# EEZ_DIB_MCU_r1B5.net
KiCad netlist of a schematic drawn in EAGLE
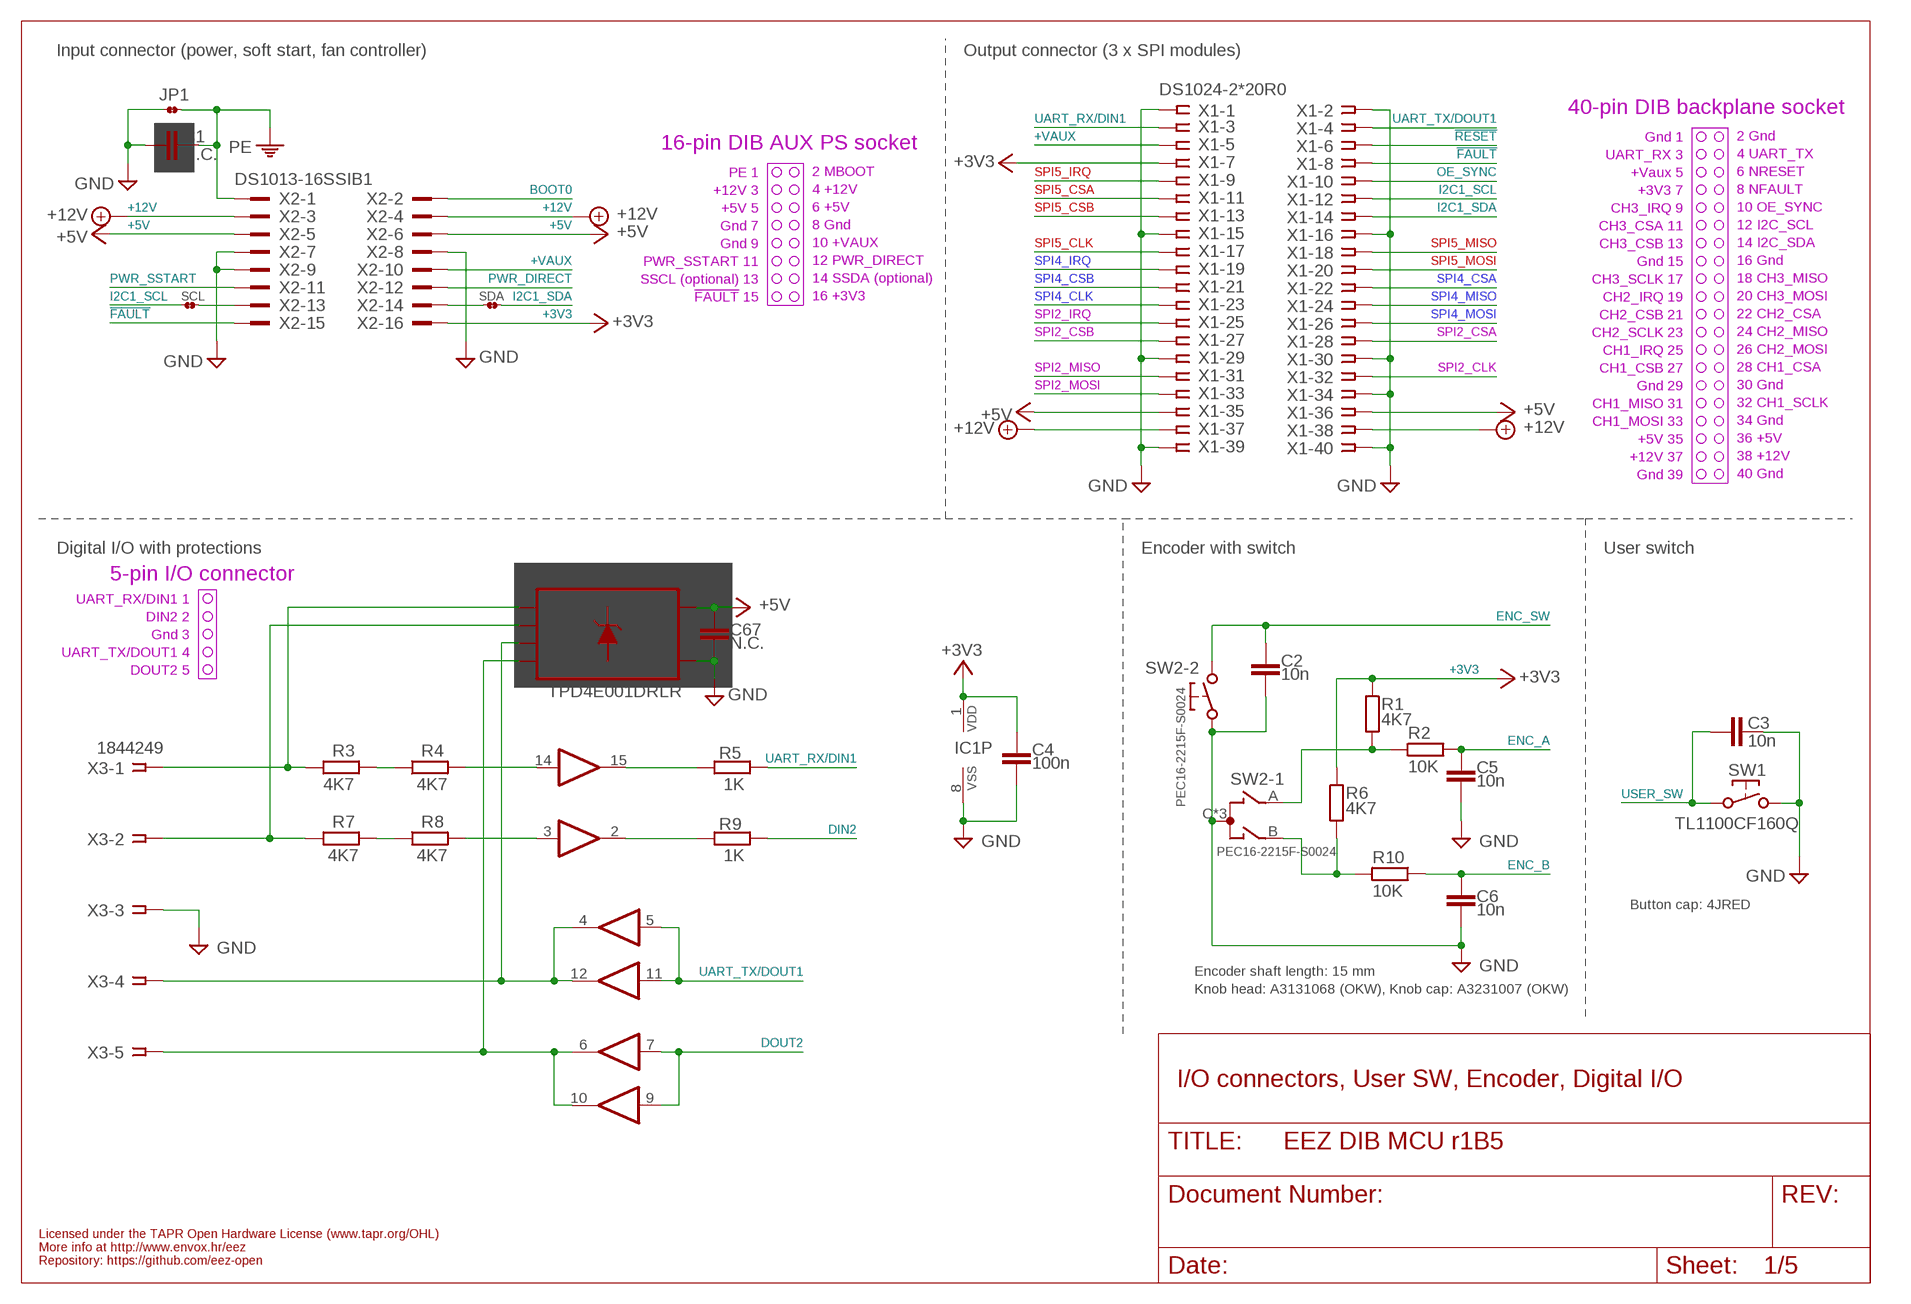
[diagram p0: schematic, sheet 1]
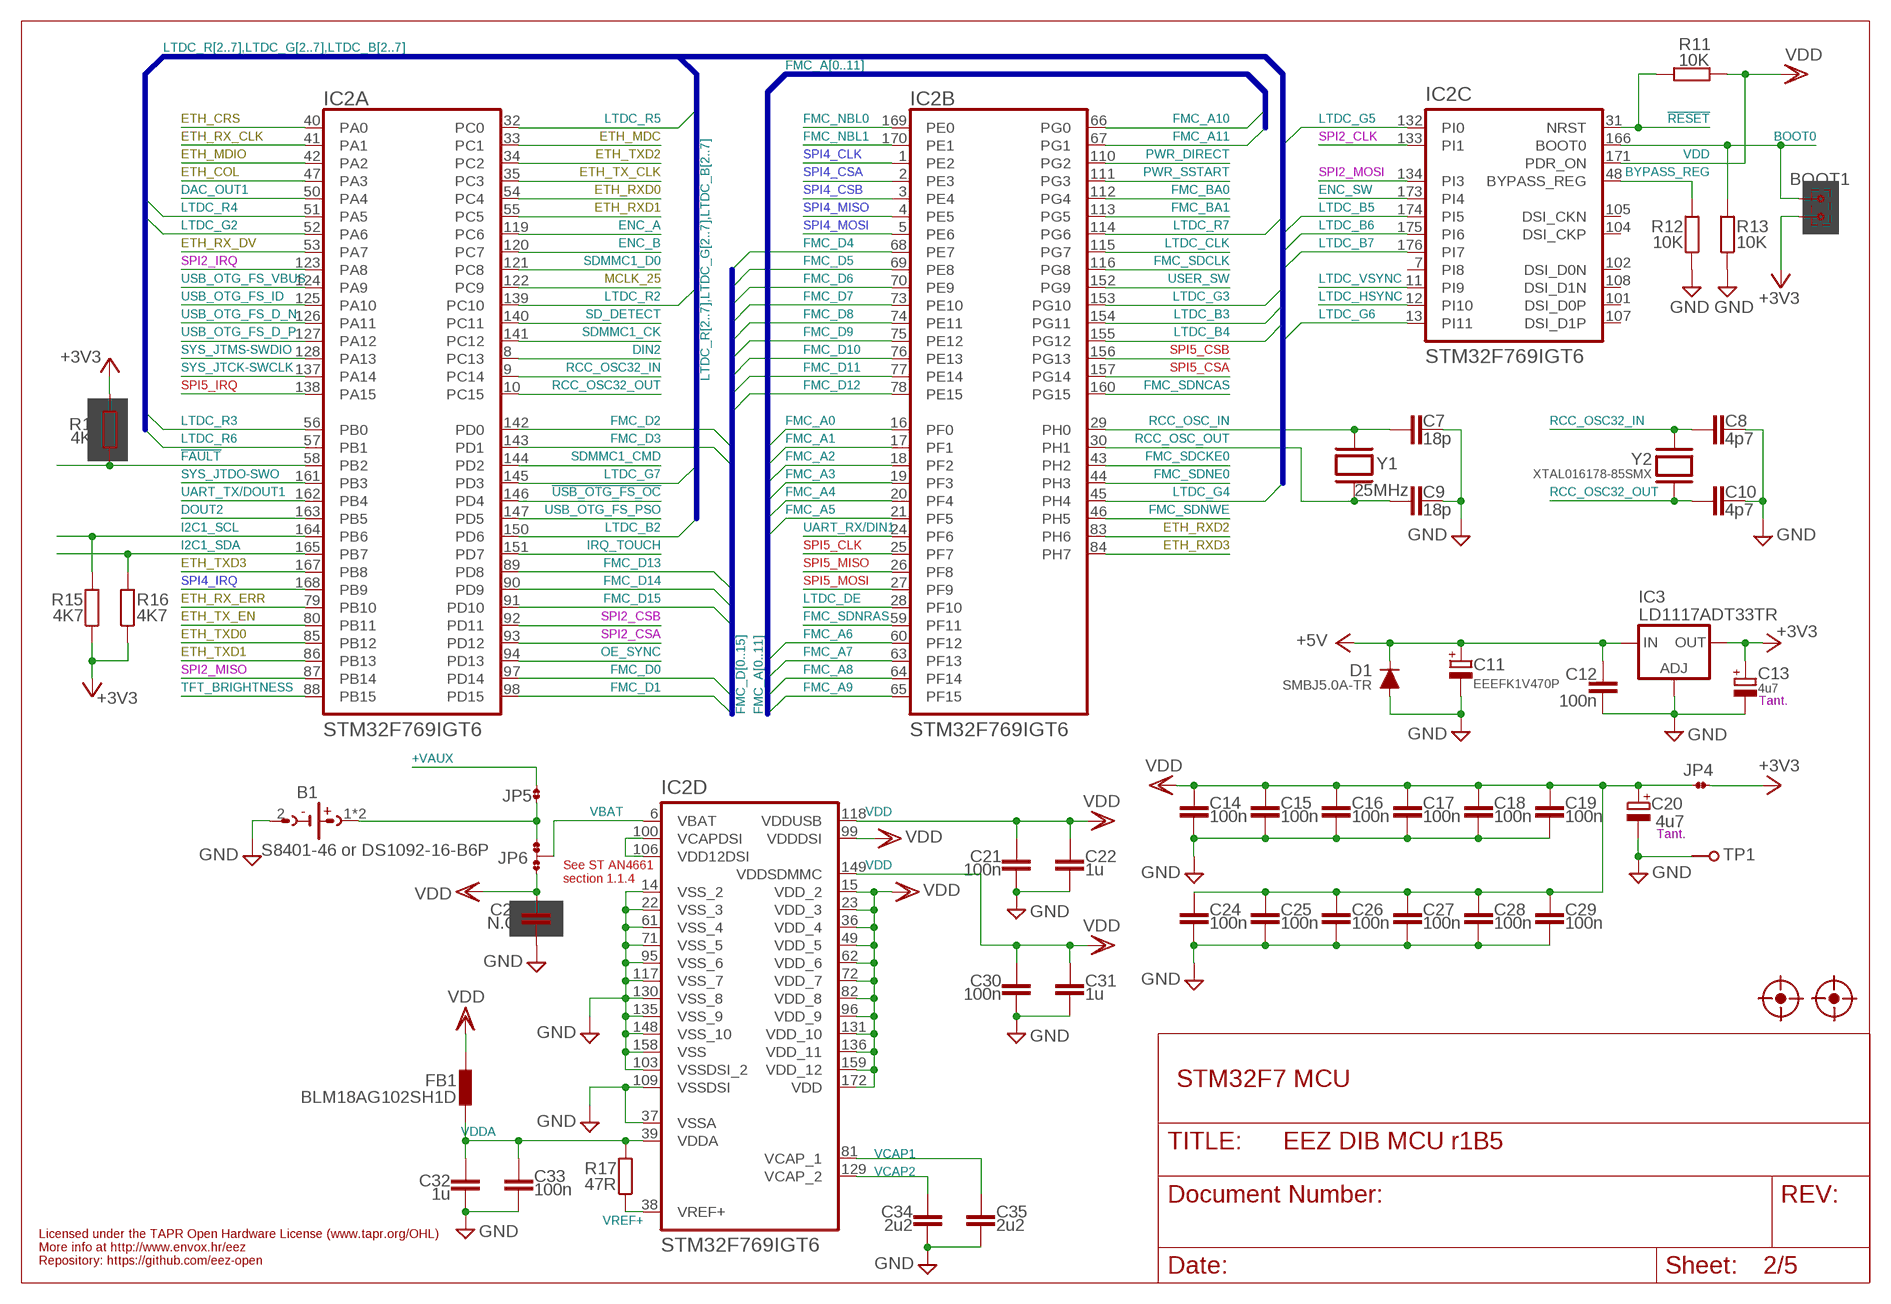
[diagram p1: schematic, sheet 2]
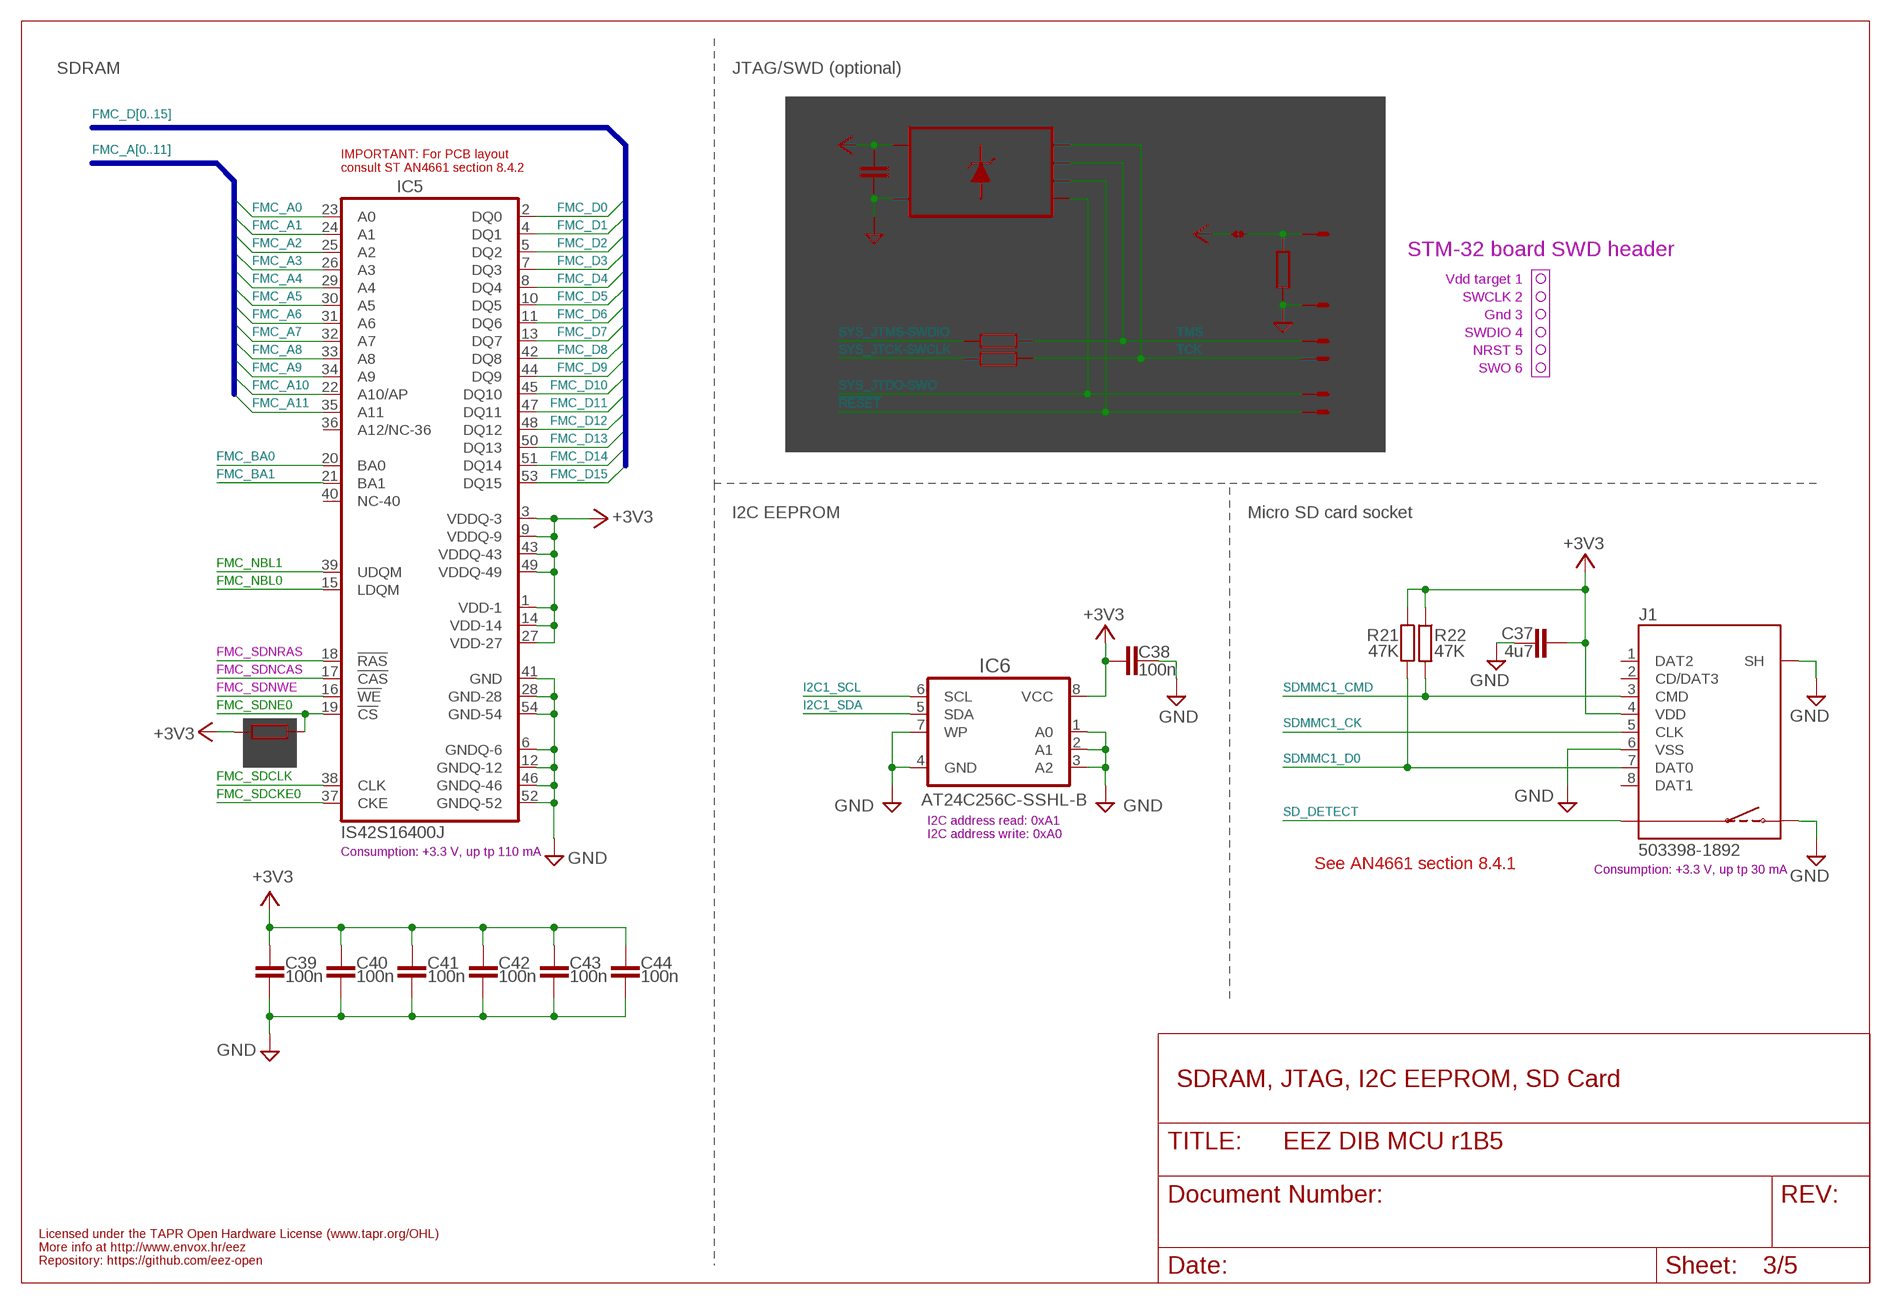
[diagram p2: schematic, sheet 3]
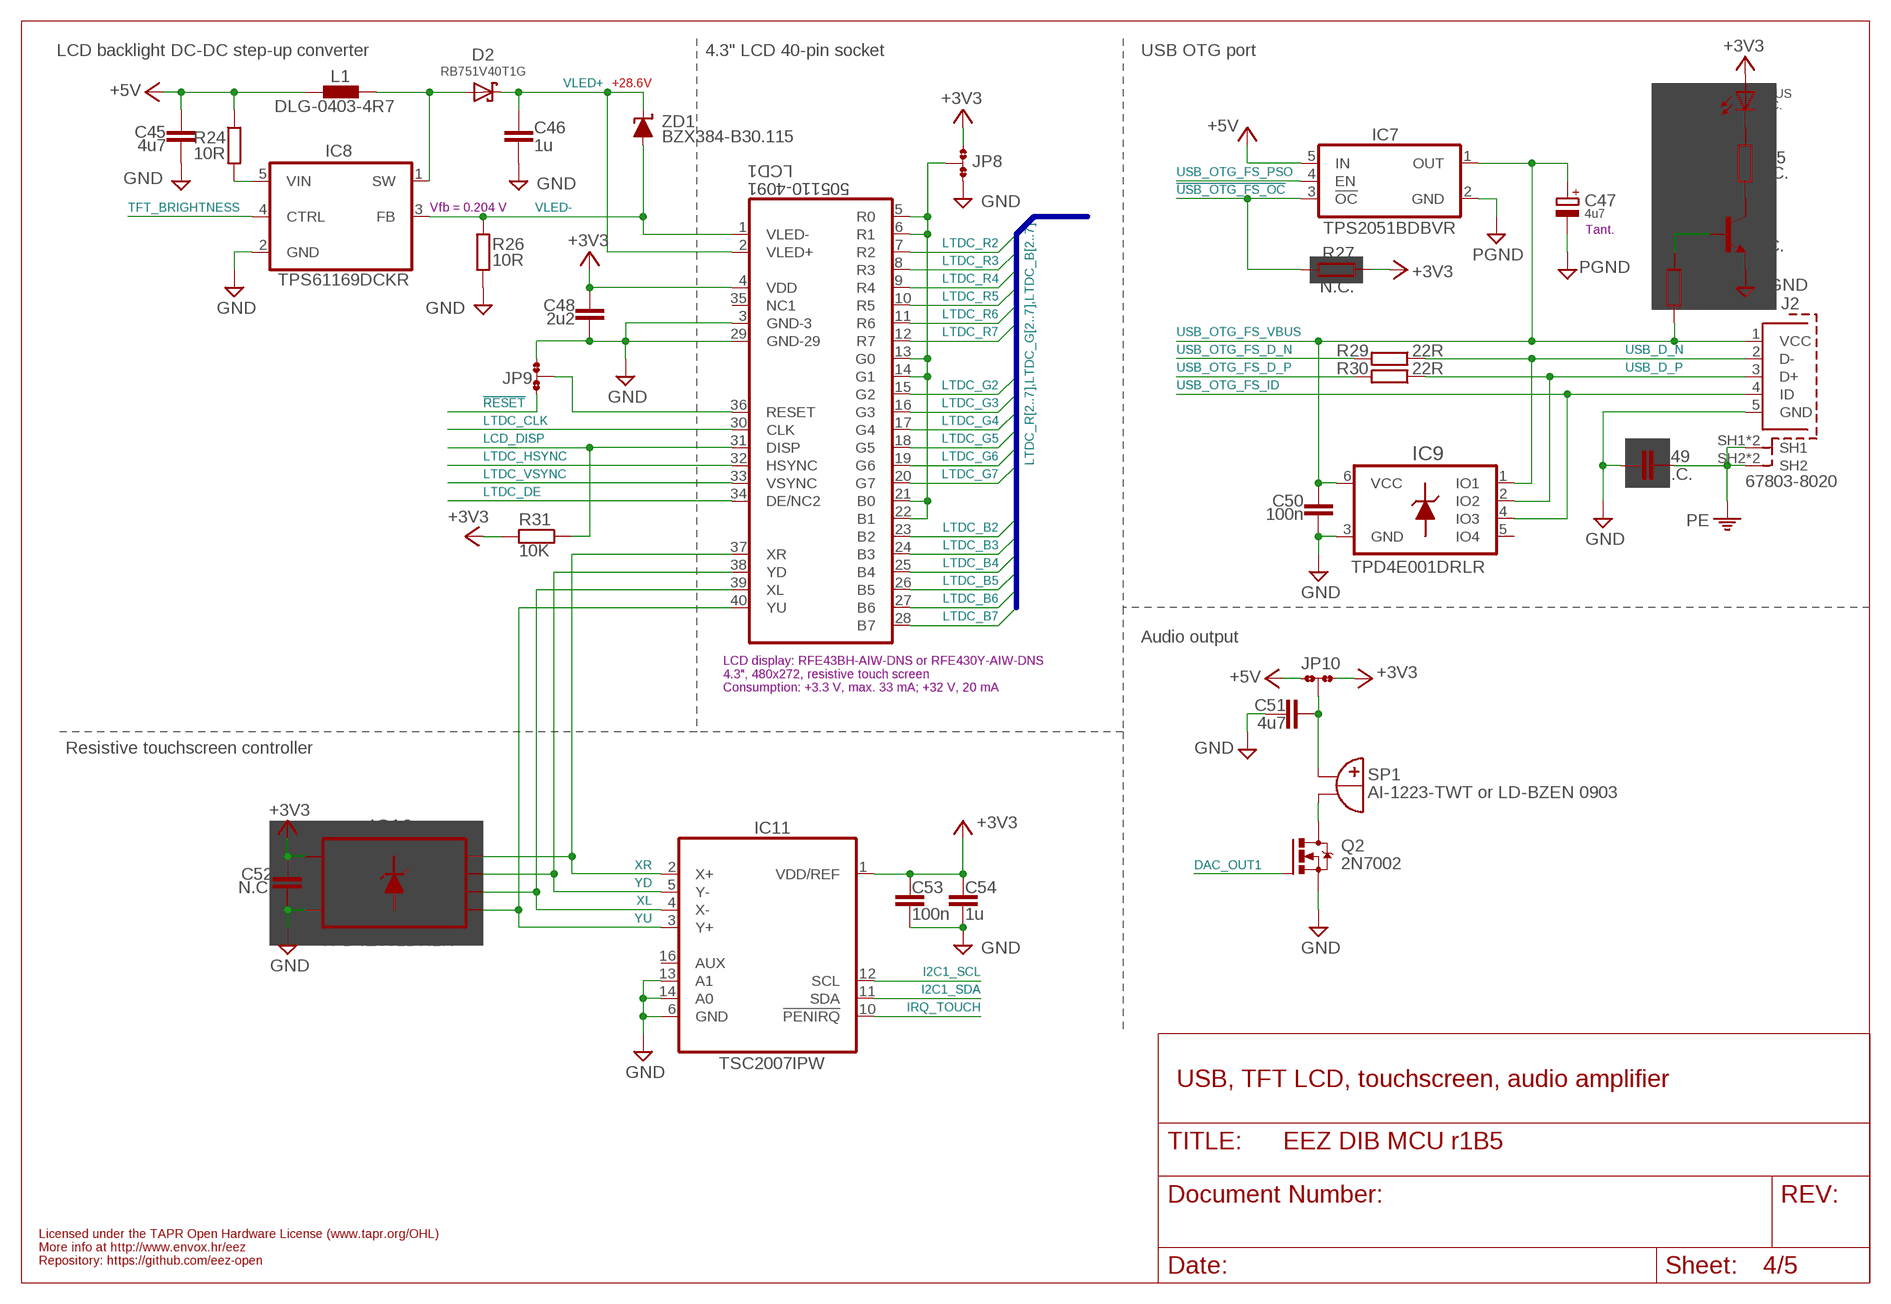
[diagram p3: schematic, sheet 4]
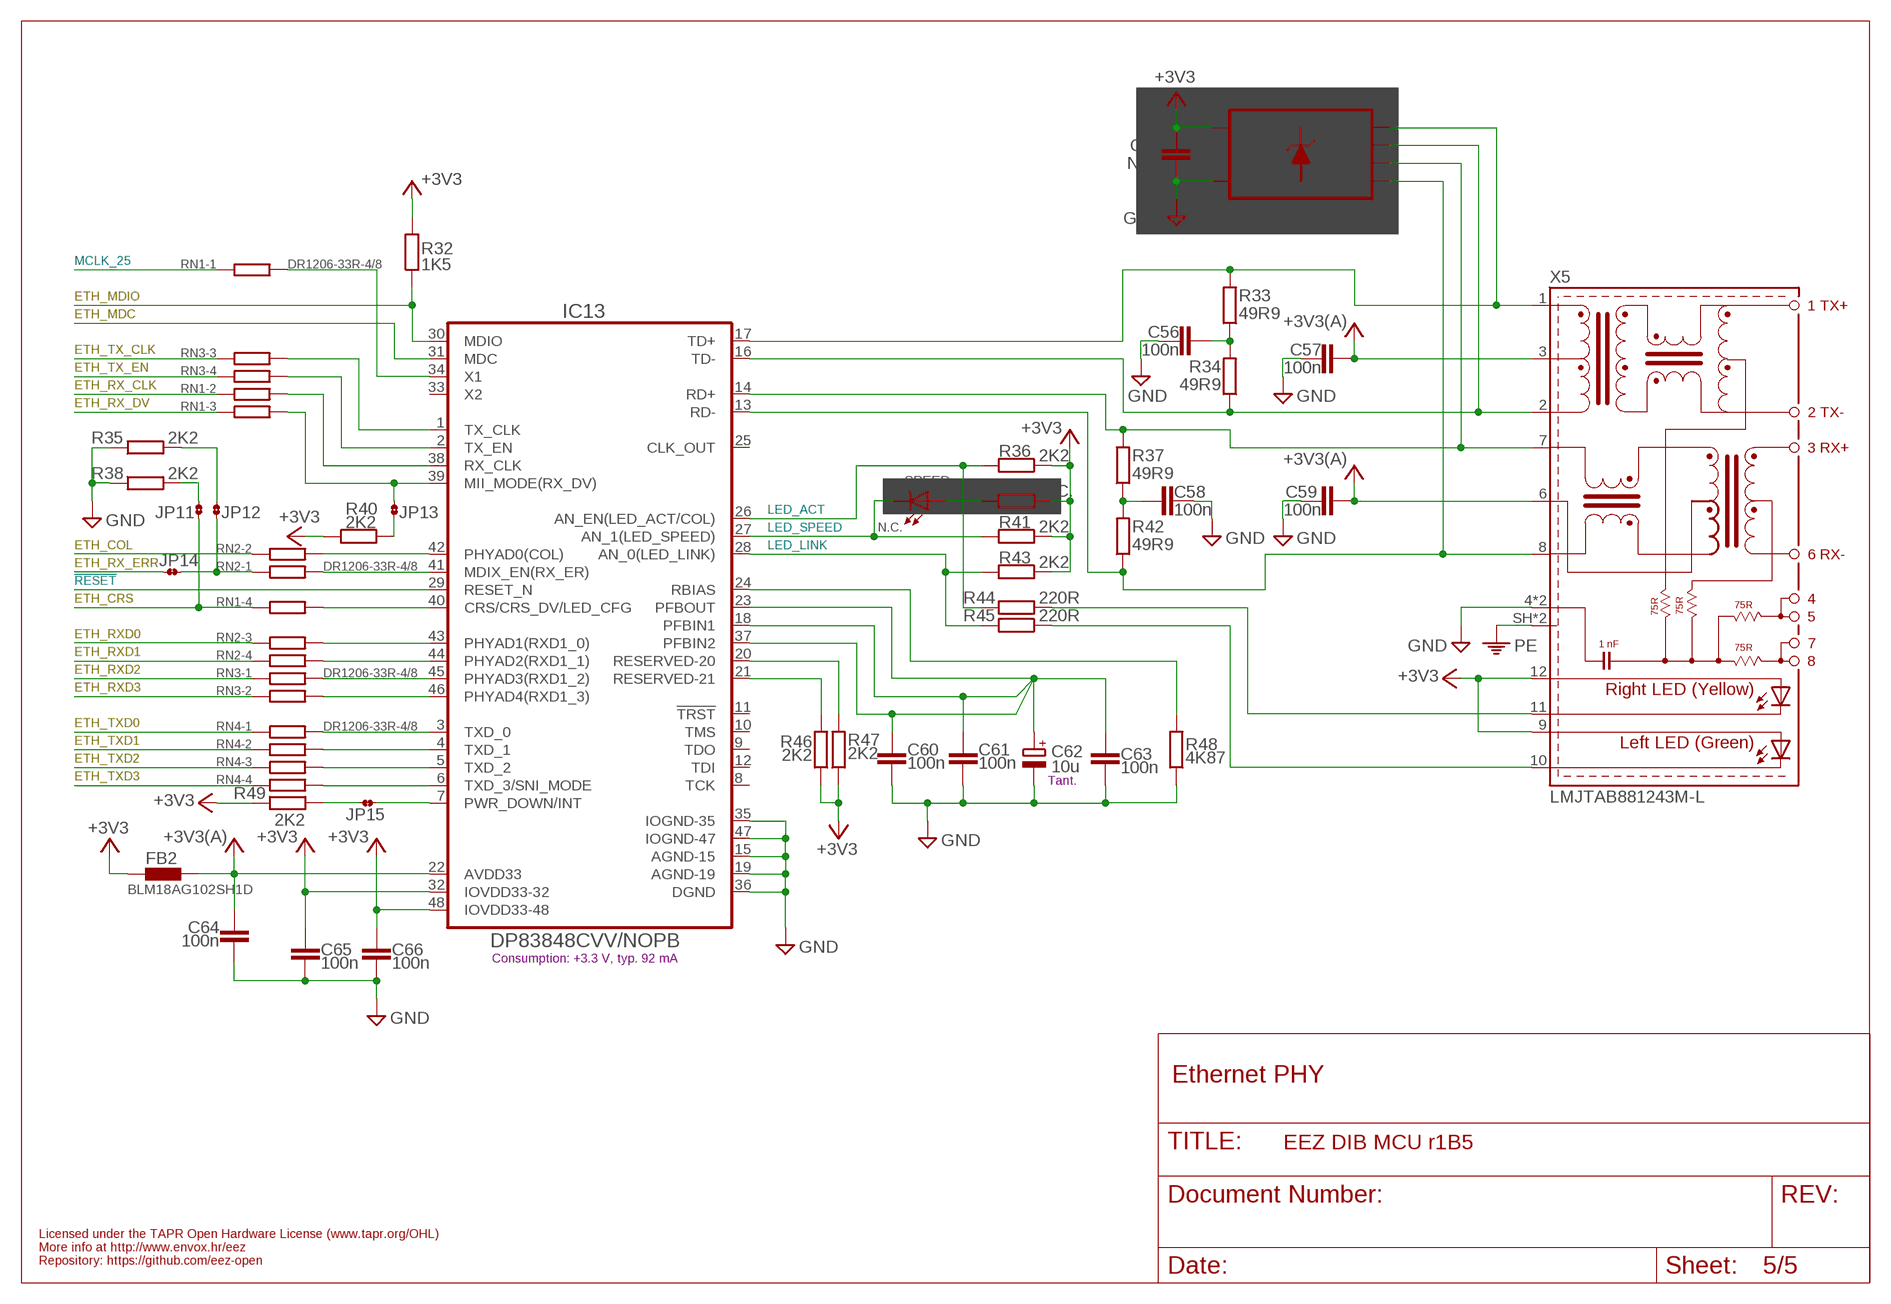
[diagram p4: schematic, sheet 5]

(export (version "E")
  (design (tool "Eeschema 10.0.6"))
  (components
    (comp (ref "C45")
      (value "4u7")
      (footprint "eagle-import:C1206")
      (libsource (lib "eagle-import") (part "C-EUC1206"))
    )
    (comp (ref "C46")
      (value "1u")
      (footprint "eagle-import:C0805")
      (libsource (lib "eagle-import") (part "C-EUC0805"))
    )
    (comp (ref "C47")
      (value "4u7")
      (footprint "eagle-import:EC1206")
      (libsource (lib "eagle-import") (part "ECAP1206"))
    )
    (comp (ref "C48")
      (value "2u2")
      (footprint "eagle-import:C0805")
      (libsource (lib "eagle-import") (part "C-EUC0805"))
    )
    (comp (ref "C49")
      (value "N.C.")
      (footprint "eagle-import:C0805")
      (libsource (lib "eagle-import") (part "C-EUC0805"))
    )
    (comp (ref "C50")
      (value "100n")
      (footprint "eagle-import:C0603")
      (libsource (lib "eagle-import") (part "C-EUC0603"))
    )
    (comp (ref "C51")
      (value "4u7")
      (footprint "eagle-import:C1206")
      (libsource (lib "eagle-import") (part "C-EUC1206"))
    )
    (comp (ref "C52")
      (value "N.C.")
      (footprint "eagle-import:C0603")
      (libsource (lib "eagle-import") (part "C-EUC0603"))
    )
    (comp (ref "C53")
      (value "100n")
      (footprint "eagle-import:C0603")
      (libsource (lib "eagle-import") (part "C-EUC0603"))
    )
    (comp (ref "C54")
      (value "1u")
      (footprint "eagle-import:C0805")
      (libsource (lib "eagle-import") (part "C-EUC0805"))
    )
    (comp (ref "D2")
      (value "RB751V40T1G")
      (footprint "eagle-import:SOD323-R")
      (libsource (lib "eagle-import") (part "SCHOTTKYSOD-323R"))
    )
    (comp (ref "IC7")
      (value "TPS2051BDBVR")
      (footprint "eagle-import:DBV5")
      (libsource (lib "eagle-import") (part "TPS2051B"))
    )
    (comp (ref "IC8")
      (value "TPS61169DCKR")
      (footprint "eagle-import:DCK5")
      (fields (field (name "MANUFACTURER") "Texas Instruments"))
      (libsource (lib "eagle-import") (part "TPS61169DCKR"))
    )
    (comp (ref "IC9")
      (value "TPD4E001DRLR")
      (footprint "eagle-import:DRL6")
      (libsource (lib "eagle-import") (part "TPD4E001-DRL"))
    )
    (comp (ref "IC10")
      (value "TPD4E001DRLR")
      (footprint "eagle-import:DRL6")
      (libsource (lib "eagle-import") (part "TPD4E001-DRL"))
    )
    (comp (ref "IC11")
      (value "TSC2007IPW")
      (footprint "eagle-import:PW(R-PDSO-G16)")
      (libsource (lib "eagle-import") (part "TSC2007IPW"))
    )
    (comp (ref "J2")
      (value "67803-8020")
      (footprint "eagle-import:678038020")
      (libsource (lib "eagle-import") (part "678038020"))
    )
    (comp (ref "JP8")
      (value "JP3-CUT")
      (footprint "eagle-import:JP3-CUT")
      (libsource (lib "eagle-import") (part "JP3-CUT"))
    )
    (comp (ref "JP9")
      (value "JP3-CUT")
      (footprint "eagle-import:JP3-CUT")
      (libsource (lib "eagle-import") (part "JP3-CUT"))
    )
    (comp (ref "JP10")
      (value "JP3-CUT")
      (footprint "eagle-import:JP3-CUT")
      (libsource (lib "eagle-import") (part "JP3-CUT"))
    )
    (comp (ref "L1")
      (value "DLG-0403-4R7")
      (footprint "eagle-import:DE0403")
      (libsource (lib "eagle-import") (part "DE0403"))
    )
    (comp (ref "LCD1")
      (value "505110-4091")
      (footprint "eagle-import:FPC_40")
      (libsource (lib "eagle-import") (part "RFE430Y-AIW-DNS"))
    )
    (comp (ref "Q1")
      (value "N.C.")
      (footprint "eagle-import:SOT23-BEC")
      (libsource (lib "eagle-import") (part "-NPN-SOT23-BECMMBT5551LT1"))
    )
    (comp (ref "Q2")
      (value "2N7002")
      (footprint "eagle-import:SOT103P240X110-3N")
      (fields (field (name "MPN") "2N7002-7-F"))
      (libsource (lib "eagle-import") (part "2N7002"))
    )
    (comp (ref "R24")
      (value "10R")
      (footprint "eagle-import:R0805")
      (libsource (lib "eagle-import") (part "R-EU_R0805"))
    )
    (comp (ref "R25")
      (value "N.C.")
      (footprint "eagle-import:R0805")
      (libsource (lib "eagle-import") (part "R-EU_R0805"))
    )
    (comp (ref "R26")
      (value "10R")
      (footprint "eagle-import:R0805")
      (libsource (lib "eagle-import") (part "R-EU_R0805"))
    )
    (comp (ref "R27")
      (value "N.C.")
      (footprint "eagle-import:R0805")
      (libsource (lib "eagle-import") (part "R-EU_R0805"))
    )
    (comp (ref "R28")
      (value "N.C.")
      (footprint "eagle-import:R0805")
      (libsource (lib "eagle-import") (part "R-EU_R0805"))
    )
    (comp (ref "R29")
      (value "22R")
      (footprint "eagle-import:R0805")
      (libsource (lib "eagle-import") (part "R-EU_R0805"))
    )
    (comp (ref "R30")
      (value "22R")
      (footprint "eagle-import:R0805")
      (libsource (lib "eagle-import") (part "R-EU_R0805"))
    )
    (comp (ref "R31")
      (value "10K")
      (footprint "eagle-import:R0805")
      (libsource (lib "eagle-import") (part "R-EU_R0805"))
    )
    (comp (ref "SP1")
      (value "AI-1223-TWT or LD-BZEN 0903")
      (footprint "eagle-import:AI-1223-TWT_COMBO")
      (libsource (lib "eagle-import") (part "AI-1223-TWT-LDB0903"))
    )
    (comp (ref "VBUS")
      (value "N.C.")
      (footprint "eagle-import:LED_0805")
      (libsource (lib "eagle-import") (part "LED0805"))
    )
    (comp (ref "ZD1")
      (value "BZX384-B30.115")
      (footprint "eagle-import:SOD323-W")
      (libsource (lib "eagle-import") (part "ZENER-DIODESOD323"))
    )
    (comp (ref "B1")
      (value "S8401-46 or DS1092-16-B6P")
      (footprint "eagle-import:S8401-46")
      (libsource (lib "eagle-import") (part "CELL_BATTERYVERT"))
    )
    (comp (ref "BOOT1")
      (value "JUMPER-2PIN-2MM")
      (footprint "eagle-import:2MM-2")
      (libsource (lib "eagle-import") (part "JUMPER-2PIN-2MM"))
    )
    (comp (ref "C7")
      (value "18p")
      (footprint "eagle-import:C0603")
      (libsource (lib "eagle-import") (part "C-EUC0603"))
    )
    (comp (ref "C8")
      (value "4p7")
      (footprint "eagle-import:C0603")
      (libsource (lib "eagle-import") (part "C-EUC0603"))
    )
    (comp (ref "C9")
      (value "18p")
      (footprint "eagle-import:C0603")
      (libsource (lib "eagle-import") (part "C-EUC0603"))
    )
    (comp (ref "C10")
      (value "4p7")
      (footprint "eagle-import:C0603")
      (libsource (lib "eagle-import") (part "C-EUC0603"))
    )
    (comp (ref "C11")
      (value "EEEFK1V470P")
      (footprint "eagle-import:CAPAE660X610N")
      (libsource (lib "eagle-import") (part "ECAPPANASONIC_H"))
    )
    (comp (ref "C12")
      (value "100n")
      (footprint "eagle-import:C0603")
      (libsource (lib "eagle-import") (part "C-EUC0603"))
    )
    (comp (ref "C13")
      (value "4u7")
      (footprint "eagle-import:EC1206")
      (libsource (lib "eagle-import") (part "ECAP1206"))
    )
    (comp (ref "C14")
      (value "100n")
      (footprint "eagle-import:C0603")
      (libsource (lib "eagle-import") (part "C-EUC0603"))
    )
    (comp (ref "C15")
      (value "100n")
      (footprint "eagle-import:C0603")
      (libsource (lib "eagle-import") (part "C-EUC0603"))
    )
    (comp (ref "C16")
      (value "100n")
      (footprint "eagle-import:C0603")
      (libsource (lib "eagle-import") (part "C-EUC0603"))
    )
    (comp (ref "C17")
      (value "100n")
      (footprint "eagle-import:C0603")
      (libsource (lib "eagle-import") (part "C-EUC0603"))
    )
    (comp (ref "C18")
      (value "100n")
      (footprint "eagle-import:C0603")
      (libsource (lib "eagle-import") (part "C-EUC0603"))
    )
    (comp (ref "C19")
      (value "100n")
      (footprint "eagle-import:C0603")
      (libsource (lib "eagle-import") (part "C-EUC0603"))
    )
    (comp (ref "C20")
      (value "4u7")
      (footprint "eagle-import:EC1206")
      (libsource (lib "eagle-import") (part "ECAP1206"))
    )
    (comp (ref "C21")
      (value "100n")
      (footprint "eagle-import:C0603")
      (libsource (lib "eagle-import") (part "C-EUC0603"))
    )
    (comp (ref "C22")
      (value "1u")
      (footprint "eagle-import:C0805")
      (libsource (lib "eagle-import") (part "C-EUC0805"))
    )
    (comp (ref "C23")
      (value "N.C.")
      (footprint "eagle-import:C0603")
      (libsource (lib "eagle-import") (part "C-EUC0603"))
    )
    (comp (ref "C24")
      (value "100n")
      (footprint "eagle-import:C0603")
      (libsource (lib "eagle-import") (part "C-EUC0603"))
    )
    (comp (ref "C25")
      (value "100n")
      (footprint "eagle-import:C0603")
      (libsource (lib "eagle-import") (part "C-EUC0603"))
    )
    (comp (ref "C26")
      (value "100n")
      (footprint "eagle-import:C0603")
      (libsource (lib "eagle-import") (part "C-EUC0603"))
    )
    (comp (ref "C27")
      (value "100n")
      (footprint "eagle-import:C0603")
      (libsource (lib "eagle-import") (part "C-EUC0603"))
    )
    (comp (ref "C28")
      (value "100n")
      (footprint "eagle-import:C0603")
      (libsource (lib "eagle-import") (part "C-EUC0603"))
    )
    (comp (ref "C29")
      (value "100n")
      (footprint "eagle-import:C0603")
      (libsource (lib "eagle-import") (part "C-EUC0603"))
    )
    (comp (ref "C30")
      (value "100n")
      (footprint "eagle-import:C0603")
      (libsource (lib "eagle-import") (part "C-EUC0603"))
    )
    (comp (ref "C31")
      (value "1u")
      (footprint "eagle-import:C0805")
      (libsource (lib "eagle-import") (part "C-EUC0805"))
    )
    (comp (ref "C32")
      (value "1u")
      (footprint "eagle-import:C0805")
      (libsource (lib "eagle-import") (part "C-EUC0805"))
    )
    (comp (ref "C33")
      (value "100n")
      (footprint "eagle-import:C0603")
      (libsource (lib "eagle-import") (part "C-EUC0603"))
    )
    (comp (ref "C34")
      (value "2u2")
      (footprint "eagle-import:C0805")
      (libsource (lib "eagle-import") (part "C-EUC0805"))
    )
    (comp (ref "C35")
      (value "2u2")
      (footprint "eagle-import:C0805")
      (libsource (lib "eagle-import") (part "C-EUC0805"))
    )
    (comp (ref "D1")
      (value "SMBJ5.0A-TR")
      (footprint "eagle-import:DO214AA")
      (libsource (lib "eagle-import") (part "DIODEDO214AA"))
    )
    (comp (ref "FB1")
      (value "BLM18AG102SH1D")
      (footprint "eagle-import:BEAD0603")
      (libsource (lib "eagle-import") (part "FERRITE_BEAD0603"))
    )
    (comp (ref "FM1")
      (value "FIDUCIAL")
      (footprint "eagle-import:FIDUCIAL")
      (libsource (lib "eagle-import") (part "FIDUCIAL"))
    )
    (comp (ref "FM2")
      (value "FIDUCIAL")
      (footprint "eagle-import:FIDUCIAL")
      (libsource (lib "eagle-import") (part "FIDUCIAL"))
    )
    (comp (ref "IC2")
      (value "STM32F769IGT6")
      (footprint "eagle-import:LQFP-176_24X24MM")
      (fields
        (field (name "MANUFACTURER_PART_NUMBER") "stm32f769ixt")
        (field (name "COPYRIGHT") "Copyright C 2016 Accelerated Designs. All rights reserved")
      )
      (libsource (lib "eagle-import") (part "STM32F769IXT"))
    )
    (comp (ref "IC3")
      (value "LD1117ADT33TR")
      (footprint "eagle-import:DPACK")
      (libsource (lib "eagle-import") (part "LD117A?DT33TR"))
    )
    (comp (ref "JP4")
      (value "JP2-NOCUT")
      (footprint "eagle-import:JP2-NOCUT")
      (libsource (lib "eagle-import") (part "JP2-NOCUT"))
    )
    (comp (ref "JP5")
      (value "JP2-CUT")
      (footprint "eagle-import:JP2-CUT")
      (libsource (lib "eagle-import") (part "JP2-CUT"))
    )
    (comp (ref "JP6")
      (value "JP3-CUT")
      (footprint "eagle-import:JP3-CUT")
      (libsource (lib "eagle-import") (part "JP3-CUT"))
    )
    (comp (ref "R11")
      (value "10K")
      (footprint "eagle-import:R0805")
      (libsource (lib "eagle-import") (part "R-EU_R0805"))
    )
    (comp (ref "R12")
      (value "10K")
      (footprint "eagle-import:R0805")
      (libsource (lib "eagle-import") (part "R-EU_R0805"))
    )
    (comp (ref "R13")
      (value "10K")
      (footprint "eagle-import:R0805")
      (libsource (lib "eagle-import") (part "R-EU_R0805"))
    )
    (comp (ref "R14")
      (value "4K7")
      (footprint "eagle-import:R0805")
      (libsource (lib "eagle-import") (part "R-EU_R0805"))
    )
    (comp (ref "R15")
      (value "4K7")
      (footprint "eagle-import:R0805")
      (libsource (lib "eagle-import") (part "R-EU_R0805"))
    )
    (comp (ref "R16")
      (value "4K7")
      (footprint "eagle-import:R0805")
      (libsource (lib "eagle-import") (part "R-EU_R0805"))
    )
    (comp (ref "R17")
      (value "47R")
      (footprint "eagle-import:R0805")
      (libsource (lib "eagle-import") (part "R-EU_R0805"))
    )
    (comp (ref "TP1")
      (value "PCB_TEST_TABSHIELD")
      (footprint "eagle-import:PCB_SHIELD_TAB")
      (libsource (lib "eagle-import") (part "PCB_TEST_TABSHIELD"))
    )
    (comp (ref "Y1")
      (value "25MHz")
      (footprint "eagle-import:HC-49_4H")
      (libsource (lib "eagle-import") (part "XTALSMD"))
    )
    (comp (ref "Y2")
      (value "XTAL016178-85SMX")
      (footprint "eagle-import:85SMX")
      (libsource (lib "eagle-import") (part "XTAL85SMX"))
    )
    (comp (ref "C1")
      (value "N.C.")
      (footprint "eagle-import:C0805")
      (libsource (lib "eagle-import") (part "C-EUC0805"))
    )
    (comp (ref "C2")
      (value "10n")
      (footprint "eagle-import:C0805")
      (libsource (lib "eagle-import") (part "C-EUC0805"))
    )
    (comp (ref "C3")
      (value "10n")
      (footprint "eagle-import:C0805")
      (libsource (lib "eagle-import") (part "C-EUC0805"))
    )
    (comp (ref "C4")
      (value "100n")
      (footprint "eagle-import:C0603")
      (libsource (lib "eagle-import") (part "C-EUC0603"))
    )
    (comp (ref "C5")
      (value "10n")
      (footprint "eagle-import:C0805")
      (libsource (lib "eagle-import") (part "C-EUC0805"))
    )
    (comp (ref "C6")
      (value "10n")
      (footprint "eagle-import:C0805")
      (libsource (lib "eagle-import") (part "C-EUC0805"))
    )
    (comp (ref "C67")
      (value "N.C.")
      (footprint "eagle-import:C0603")
      (libsource (lib "eagle-import") (part "C-EUC0603"))
    )
    (comp (ref "IC1")
      (value "CD74HC4050PWR")
      (footprint "eagle-import:PW16")
      (libsource (lib "eagle-import") (part "CD74HC4050PWR"))
    )
    (comp (ref "IC14")
      (value "TPD4E001DRLR")
      (footprint "eagle-import:DRL6")
      (libsource (lib "eagle-import") (part "TPD4E001-DRL"))
    )
    (comp (ref "JP1")
      (value "JP2-NOCUT")
      (footprint "eagle-import:JP2-NOCUT")
      (libsource (lib "eagle-import") (part "JP2-NOCUT"))
    )
    (comp (ref "R1")
      (value "4K7")
      (footprint "eagle-import:R0805")
      (libsource (lib "eagle-import") (part "R-EU_R0805"))
    )
    (comp (ref "R2")
      (value "10K")
      (footprint "eagle-import:R0805")
      (libsource (lib "eagle-import") (part "R-EU_R0805"))
    )
    (comp (ref "R3")
      (value "4K7")
      (footprint "eagle-import:R0805")
      (libsource (lib "eagle-import") (part "R-EU_R0805"))
    )
    (comp (ref "R4")
      (value "4K7")
      (footprint "eagle-import:R0805")
      (libsource (lib "eagle-import") (part "R-EU_R0805"))
    )
    (comp (ref "R5")
      (value "1K")
      (footprint "eagle-import:R0805")
      (libsource (lib "eagle-import") (part "R-EU_R0805"))
    )
    (comp (ref "R6")
      (value "4K7")
      (footprint "eagle-import:R0805")
      (libsource (lib "eagle-import") (part "R-EU_R0805"))
    )
    (comp (ref "R7")
      (value "4K7")
      (footprint "eagle-import:R0805")
      (libsource (lib "eagle-import") (part "R-EU_R0805"))
    )
    (comp (ref "R8")
      (value "4K7")
      (footprint "eagle-import:R0805")
      (libsource (lib "eagle-import") (part "R-EU_R0805"))
    )
    (comp (ref "R9")
      (value "1K")
      (footprint "eagle-import:R0805")
      (libsource (lib "eagle-import") (part "R-EU_R0805"))
    )
    (comp (ref "R10")
      (value "10K")
      (footprint "eagle-import:R0805")
      (libsource (lib "eagle-import") (part "R-EU_R0805"))
    )
    (comp (ref "SCL")
      (value "JP2-NOCUT")
      (footprint "eagle-import:JP2-NOCUT")
      (libsource (lib "eagle-import") (part "JP2-NOCUT"))
    )
    (comp (ref "SDA")
      (value "JP2-NOCUT")
      (footprint "eagle-import:JP2-NOCUT")
      (libsource (lib "eagle-import") (part "JP2-NOCUT"))
    )
    (comp (ref "SW1")
      (value "TL1100CF160Q")
      (footprint "eagle-import:TL1100C")
      (libsource (lib "eagle-import") (part "TL1100C"))
    )
    (comp (ref "SW2")
      (value "PEC16-2215F-S0024")
      (footprint "eagle-import:PEC16-2215F")
      (libsource (lib "eagle-import") (part "ENCODER_SW-PEC16"))
    )
    (comp (ref "X1")
      (value "DS1024-2*20R0")
      (footprint "eagle-import:ZL263-40DG")
      (libsource (lib "eagle-import") (part "ZL263-40DG"))
    )
    (comp (ref "X2")
      (value "DS1013-16SSIB1")
      (footprint "eagle-import:IDC-16PIN")
      (libsource (lib "eagle-import") (part "IDC-16PIN"))
    )
    (comp (ref "X3")
      (value "1844249")
      (footprint "eagle-import:MC1,5_5-G-3,5")
      (libsource (lib "eagle-import") (part "MC1,5/5-G-3,5"))
    )
    (comp (ref "C36")
      (value "N.C.")
      (footprint "eagle-import:C0603")
      (libsource (lib "eagle-import") (part "C-EUC0603"))
    )
    (comp (ref "C37")
      (value "4u7")
      (footprint "eagle-import:C1206")
      (libsource (lib "eagle-import") (part "C-EUC1206"))
    )
    (comp (ref "C38")
      (value "100n")
      (footprint "eagle-import:C0603")
      (libsource (lib "eagle-import") (part "C-EUC0603"))
    )
    (comp (ref "C39")
      (value "100n")
      (footprint "eagle-import:C0603")
      (libsource (lib "eagle-import") (part "C-EUC0603"))
    )
    (comp (ref "C40")
      (value "100n")
      (footprint "eagle-import:C0603")
      (libsource (lib "eagle-import") (part "C-EUC0603"))
    )
    (comp (ref "C41")
      (value "100n")
      (footprint "eagle-import:C0603")
      (libsource (lib "eagle-import") (part "C-EUC0603"))
    )
    (comp (ref "C42")
      (value "100n")
      (footprint "eagle-import:C0603")
      (libsource (lib "eagle-import") (part "C-EUC0603"))
    )
    (comp (ref "C43")
      (value "100n")
      (footprint "eagle-import:C0603")
      (libsource (lib "eagle-import") (part "C-EUC0603"))
    )
    (comp (ref "C44")
      (value "100n")
      (footprint "eagle-import:C0603")
      (libsource (lib "eagle-import") (part "C-EUC0603"))
    )
    (comp (ref "IC4")
      (value "TPD4E001DRLR")
      (footprint "eagle-import:DRL6")
      (libsource (lib "eagle-import") (part "TPD4E001-DRL"))
    )
    (comp (ref "IC5")
      (value "IS42S16400J")
      (footprint "eagle-import:TSOPII-54")
      (libsource (lib "eagle-import") (part "IS42S16400"))
    )
    (comp (ref "IC6")
      (value "AT24C256C-SSHL-B")
      (footprint "eagle-import:SOIC127P600X173-8N")
      (libsource (lib "eagle-import") (part "AT24CXXSOIC8"))
    )
    (comp (ref "J1")
      (value "503398-1892")
      (footprint "eagle-import:5033981892")
      (libsource (lib "eagle-import") (part "5033981892"))
    )
    (comp (ref "JP7")
      (value "JP2-CUT")
      (footprint "eagle-import:JP2-CUT")
      (libsource (lib "eagle-import") (part "JP2-CUT"))
    )
    (comp (ref "R18")
      (value "N.C.")
      (footprint "eagle-import:R0805")
      (libsource (lib "eagle-import") (part "R-EU_R0805"))
    )
    (comp (ref "R19")
      (value "N.C.")
      (footprint "eagle-import:R0805")
      (libsource (lib "eagle-import") (part "R-EU_R0805"))
    )
    (comp (ref "R20")
      (value "N.C.")
      (footprint "eagle-import:R0805")
      (libsource (lib "eagle-import") (part "R-EU_R0805"))
    )
    (comp (ref "R21")
      (value "47K")
      (footprint "eagle-import:R0805")
      (libsource (lib "eagle-import") (part "R-EU_R0805"))
    )
    (comp (ref "R22")
      (value "47K")
      (footprint "eagle-import:R0805")
      (libsource (lib "eagle-import") (part "R-EU_R0805"))
    )
    (comp (ref "R23")
      (value "N.C.")
      (footprint "eagle-import:R0805")
      (libsource (lib "eagle-import") (part "R-EU_R0805"))
    )
    (comp (ref "X4")
      (value "N.C.")
      (footprint "eagle-import:22-23-2061")
      (fields (field (name "MF") "MOLEX") (field (name "MPN") "22-23-2061"))
      (libsource (lib "eagle-import") (part "22-23-2061"))
    )
    (comp (ref "C55")
      (value "N.C.")
      (footprint "eagle-import:C0603")
      (libsource (lib "eagle-import") (part "C-EUC0603"))
    )
    (comp (ref "C56")
      (value "100n")
      (footprint "eagle-import:C0603")
      (libsource (lib "eagle-import") (part "C-EUC0603"))
    )
    (comp (ref "C57")
      (value "100n")
      (footprint "eagle-import:C0603")
      (libsource (lib "eagle-import") (part "C-EUC0603"))
    )
    (comp (ref "C58")
      (value "100n")
      (footprint "eagle-import:C0603")
      (libsource (lib "eagle-import") (part "C-EUC0603"))
    )
    (comp (ref "C59")
      (value "100n")
      (footprint "eagle-import:C0603")
      (libsource (lib "eagle-import") (part "C-EUC0603"))
    )
    (comp (ref "C60")
      (value "100n")
      (footprint "eagle-import:C0603")
      (libsource (lib "eagle-import") (part "C-EUC0603"))
    )
    (comp (ref "C61")
      (value "100n")
      (footprint "eagle-import:C0603")
      (libsource (lib "eagle-import") (part "C-EUC0603"))
    )
    (comp (ref "C62")
      (value "10u")
      (footprint "eagle-import:EC1206")
      (libsource (lib "eagle-import") (part "ECAP1206"))
    )
    (comp (ref "C63")
      (value "100n")
      (footprint "eagle-import:C0603")
      (libsource (lib "eagle-import") (part "C-EUC0603"))
    )
    (comp (ref "C64")
      (value "100n")
      (footprint "eagle-import:C0603")
      (libsource (lib "eagle-import") (part "C-EUC0603"))
    )
    (comp (ref "C65")
      (value "100n")
      (footprint "eagle-import:C0603")
      (libsource (lib "eagle-import") (part "C-EUC0603"))
    )
    (comp (ref "C66")
      (value "100n")
      (footprint "eagle-import:C0603")
      (libsource (lib "eagle-import") (part "C-EUC0603"))
    )
    (comp (ref "FB2")
      (value "BLM18AG102SH1D")
      (footprint "eagle-import:BEAD0603")
      (libsource (lib "eagle-import") (part "FERRITE_BEAD0603"))
    )
    (comp (ref "IC12")
      (value "TPD4E001DRLR")
      (footprint "eagle-import:DRL6")
      (libsource (lib "eagle-import") (part "TPD4E001-DRL"))
    )
    (comp (ref "IC13")
      (value "DP83848CVV/NOPB")
      (footprint "eagle-import:PT48")
      (libsource (lib "eagle-import") (part "DP83848CVV/NOPB"))
    )
    (comp (ref "JP11")
      (value "JP2-CUT")
      (footprint "eagle-import:JP2-CUT")
      (libsource (lib "eagle-import") (part "JP2-CUT"))
    )
    (comp (ref "JP12")
      (value "JP2-CUT")
      (footprint "eagle-import:JP2-CUT")
      (libsource (lib "eagle-import") (part "JP2-CUT"))
    )
    (comp (ref "JP13")
      (value "JP2-CUT")
      (footprint "eagle-import:JP2-CUT")
      (libsource (lib "eagle-import") (part "JP2-CUT"))
    )
    (comp (ref "JP14")
      (value "JP2-NOCUT")
      (footprint "eagle-import:JP2-NOCUT")
      (libsource (lib "eagle-import") (part "JP2-NOCUT"))
    )
    (comp (ref "JP15")
      (value "JP2-NOCUT")
      (footprint "eagle-import:JP2-NOCUT")
      (libsource (lib "eagle-import") (part "JP2-NOCUT"))
    )
    (comp (ref "R32")
      (value "1K5")
      (footprint "eagle-import:R0805")
      (libsource (lib "eagle-import") (part "R-EU_R0805"))
    )
    (comp (ref "R33")
      (value "49R9")
      (footprint "eagle-import:R0805")
      (libsource (lib "eagle-import") (part "R-EU_R0805"))
    )
    (comp (ref "R34")
      (value "49R9")
      (footprint "eagle-import:R0805")
      (libsource (lib "eagle-import") (part "R-EU_R0805"))
    )
    (comp (ref "R35")
      (value "2K2")
      (footprint "eagle-import:R0805")
      (libsource (lib "eagle-import") (part "R-EU_R0805"))
    )
    (comp (ref "R36")
      (value "2K2")
      (footprint "eagle-import:R0805")
      (libsource (lib "eagle-import") (part "R-EU_R0805"))
    )
    (comp (ref "R37")
      (value "49R9")
      (footprint "eagle-import:R0805")
      (libsource (lib "eagle-import") (part "R-EU_R0805"))
    )
    (comp (ref "R38")
      (value "2K2")
      (footprint "eagle-import:R0805")
      (libsource (lib "eagle-import") (part "R-EU_R0805"))
    )
    (comp (ref "R39")
      (value "N.C.")
      (footprint "eagle-import:R0805")
      (libsource (lib "eagle-import") (part "R-EU_R0805"))
    )
    (comp (ref "R40")
      (value "2K2")
      (footprint "eagle-import:R0805")
      (libsource (lib "eagle-import") (part "R-EU_R0805"))
    )
    (comp (ref "R41")
      (value "2K2")
      (footprint "eagle-import:R0805")
      (libsource (lib "eagle-import") (part "R-EU_R0805"))
    )
    (comp (ref "R42")
      (value "49R9")
      (footprint "eagle-import:R0805")
      (libsource (lib "eagle-import") (part "R-EU_R0805"))
    )
    (comp (ref "R43")
      (value "2K2")
      (footprint "eagle-import:R0805")
      (libsource (lib "eagle-import") (part "R-EU_R0805"))
    )
    (comp (ref "R44")
      (value "220R")
      (footprint "eagle-import:R0805")
      (libsource (lib "eagle-import") (part "R-EU_R0805"))
    )
    (comp (ref "R45")
      (value "220R")
      (footprint "eagle-import:R0805")
      (libsource (lib "eagle-import") (part "R-EU_R0805"))
    )
    (comp (ref "R46")
      (value "2K2")
      (footprint "eagle-import:R0805")
      (libsource (lib "eagle-import") (part "R-EU_R0805"))
    )
    (comp (ref "R47")
      (value "2K2")
      (footprint "eagle-import:R0805")
      (libsource (lib "eagle-import") (part "R-EU_R0805"))
    )
    (comp (ref "R48")
      (value "4K87")
      (footprint "eagle-import:R0805")
      (libsource (lib "eagle-import") (part "R-EU_R0805"))
    )
    (comp (ref "R49")
      (value "2K2")
      (footprint "eagle-import:R0805")
      (libsource (lib "eagle-import") (part "R-EU_R0805"))
    )
    (comp (ref "RN1")
      (value "DR1206-33R-4/8")
      (footprint "eagle-import:CAY16")
      (libsource (lib "eagle-import") (part "R_ARRAY4"))
    )
    (comp (ref "RN2")
      (value "DR1206-33R-4/8")
      (footprint "eagle-import:CAY16")
      (libsource (lib "eagle-import") (part "R_ARRAY4"))
    )
    (comp (ref "RN3")
      (value "DR1206-33R-4/8")
      (footprint "eagle-import:CAY16")
      (libsource (lib "eagle-import") (part "R_ARRAY4"))
    )
    (comp (ref "RN4")
      (value "DR1206-33R-4/8")
      (footprint "eagle-import:CAY16")
      (libsource (lib "eagle-import") (part "R_ARRAY4"))
    )
    (comp (ref "SPEED")
      (value "N.C.")
      (footprint "eagle-import:LED_0805")
      (libsource (lib "eagle-import") (part "LED0805"))
    )
    (comp (ref "X5")
      (value "LMJTAB881243M-L")
      (footprint "eagle-import:RJ45-TRAFO-LED")
      (libsource (lib "eagle-import") (part "RJ45-TRAFO-LED"))
    )
  )
  (nets
    (net (code "1") (name "+3V3") (class "Default")
      (node (ref "BOOT1") (pin "2") (pinfunction "2_2") (pintype "passive"))
      (node (ref "C13") (pin "+") (pinfunction "+_+") (pintype "passive"))
      (node (ref "C36") (pin "1") (pinfunction "1_1") (pintype "passive"))
      (node (ref "C37") (pin "1") (pinfunction "1_1") (pintype "passive"))
      (node (ref "C38") (pin "2") (pinfunction "2_2") (pintype "passive"))
      (node (ref "C39") (pin "1") (pinfunction "1_1") (pintype "passive"))
      (node (ref "C4") (pin "1") (pinfunction "1_1") (pintype "passive"))
      (node (ref "C40") (pin "1") (pinfunction "1_1") (pintype "passive"))
      (node (ref "C41") (pin "1") (pinfunction "1_1") (pintype "passive"))
      (node (ref "C42") (pin "1") (pinfunction "1_1") (pintype "passive"))
      (node (ref "C43") (pin "1") (pinfunction "1_1") (pintype "passive"))
      (node (ref "C44") (pin "1") (pinfunction "1_1") (pintype "passive"))
      (node (ref "C48") (pin "1") (pinfunction "1_1") (pintype "passive"))
      (node (ref "C52") (pin "2") (pinfunction "2_2") (pintype "passive"))
      (node (ref "C53") (pin "2") (pinfunction "2_2") (pintype "passive"))
      (node (ref "C54") (pin "2") (pinfunction "2_2") (pintype "passive"))
      (node (ref "C55") (pin "1") (pinfunction "1_1") (pintype "passive"))
      (node (ref "C65") (pin "1") (pinfunction "1_1") (pintype "passive"))
      (node (ref "C66") (pin "1") (pinfunction "1_1") (pintype "passive"))
      (node (ref "FB2") (pin "P$1") (pinfunction "1_P$1") (pintype "passive"))
      (node (ref "IC1") (pin "1") (pinfunction "VDD_1") (pintype "power_in"))
      (node (ref "IC10") (pin "6") (pinfunction "VCC_6") (pintype "passive"))
      (node (ref "IC11") (pin "1") (pinfunction "VDD/REF_1") (pintype "passive"))
      (node (ref "IC12") (pin "6") (pinfunction "VCC_6") (pintype "passive"))
      (node (ref "IC13") (pin "32") (pinfunction "IOVDD33-32_32") (pintype "power_in"))
      (node (ref "IC13") (pin "48") (pinfunction "IOVDD33-48_48") (pintype "power_in"))
      (node (ref "IC3") (pin "4") (pinfunction "OUT_4") (pintype "passive"))
      (node (ref "IC4") (pin "6") (pinfunction "VCC_6") (pintype "passive"))
      (node (ref "IC5") (pin "1") (pinfunction "VDD-1_1") (pintype "power_in"))
      (node (ref "IC5") (pin "14") (pinfunction "VDD-14_14") (pintype "power_in"))
      (node (ref "IC5") (pin "27") (pinfunction "VDD-27_27") (pintype "power_in"))
      (node (ref "IC5") (pin "3") (pinfunction "VDDQ-3_3") (pintype "power_in"))
      (node (ref "IC5") (pin "43") (pinfunction "VDDQ-43_43") (pintype "power_in"))
      (node (ref "IC5") (pin "49") (pinfunction "VDDQ-49_49") (pintype "power_in"))
      (node (ref "IC5") (pin "9") (pinfunction "VDDQ-9_9") (pintype "power_in"))
      (node (ref "IC6") (pin "8") (pinfunction "VCC_8") (pintype "power_in"))
      (node (ref "J1") (pin "4") (pinfunction "VDD_4") (pintype "power_in"))
      (node (ref "JP10") (pin "NC") (pinfunction "NC_NC") (pintype "passive"))
      (node (ref "JP4") (pin "2") (pinfunction "2_2") (pintype "passive"))
      (node (ref "JP7") (pin "1") (pinfunction "1_1") (pintype "passive"))
      (node (ref "JP8") (pin "NO") (pinfunction "NO_NO") (pintype "passive"))
      (node (ref "LCD1") (pin "4") (pinfunction "VDD_4") (pintype "power_in"))
      (node (ref "R1") (pin "1") (pinfunction "1_1") (pintype "passive"))
      (node (ref "R14") (pin "1") (pinfunction "1_1") (pintype "passive"))
      (node (ref "R15") (pin "1") (pinfunction "1_1") (pintype "passive"))
      (node (ref "R16") (pin "1") (pinfunction "1_1") (pintype "passive"))
      (node (ref "R21") (pin "1") (pinfunction "1_1") (pintype "passive"))
      (node (ref "R22") (pin "1") (pinfunction "1_1") (pintype "passive"))
      (node (ref "R23") (pin "1") (pinfunction "1_1") (pintype "passive"))
      (node (ref "R27") (pin "2") (pinfunction "2_2") (pintype "passive"))
      (node (ref "R31") (pin "2") (pinfunction "2_2") (pintype "passive"))
      (node (ref "R32") (pin "2") (pinfunction "2_2") (pintype "passive"))
      (node (ref "R36") (pin "1") (pinfunction "1_1") (pintype "passive"))
      (node (ref "R39") (pin "1") (pinfunction "1_1") (pintype "passive"))
      (node (ref "R40") (pin "1") (pinfunction "1_1") (pintype "passive"))
      (node (ref "R41") (pin "1") (pinfunction "1_1") (pintype "passive"))
      (node (ref "R43") (pin "1") (pinfunction "1_1") (pintype "passive"))
      (node (ref "R46") (pin "1") (pinfunction "1_1") (pintype "passive"))
      (node (ref "R47") (pin "1") (pinfunction "1_1") (pintype "passive"))
      (node (ref "R49") (pin "1") (pinfunction "1_1") (pintype "passive"))
      (node (ref "R6") (pin "1") (pinfunction "1_1") (pintype "passive"))
      (node (ref "VBUS") (pin "A") (pinfunction "A_A") (pintype "passive"))
      (node (ref "X1") (pin "7") (pinfunction "1_7") (pintype "passive"))
      (node (ref "X2") (pin "16") (pinfunction "1_16") (pintype "passive"))
      (node (ref "X5") (pin "12") (pinfunction "YELLOW_A_12") (pintype "passive"))
      (node (ref "X5") (pin "9") (pinfunction "GREEN-A_9") (pintype "passive"))
    )
    (net (code "2") (name "+3V3(A)") (class "Default")
      (node (ref "C57") (pin "2") (pinfunction "2_2") (pintype "passive"))
      (node (ref "C59") (pin "2") (pinfunction "2_2") (pintype "passive"))
      (node (ref "C64") (pin "1") (pinfunction "1_1") (pintype "passive"))
      (node (ref "FB2") (pin "P$2") (pinfunction "2_P$2") (pintype "passive"))
      (node (ref "IC13") (pin "22") (pinfunction "AVDD33_22") (pintype "power_in"))
      (node (ref "X5") (pin "3") (pinfunction "CT_3") (pintype "input"))
      (node (ref "X5") (pin "6") (pinfunction "CR_6") (pintype "input"))
    )
    (net (code "3") (name "+5V") (class "Default")
      (node (ref "C11") (pin "1") (pinfunction "+_1") (pintype "passive"))
      (node (ref "C12") (pin "1") (pinfunction "1_1") (pintype "passive"))
      (node (ref "C45") (pin "1") (pinfunction "1_1") (pintype "passive"))
      (node (ref "C67") (pin "1") (pinfunction "1_1") (pintype "passive"))
      (node (ref "D1") (pin "C") (pinfunction "C_C") (pintype "passive"))
      (node (ref "IC14") (pin "6") (pinfunction "VCC_6") (pintype "passive"))
      (node (ref "IC3") (pin "3") (pinfunction "IN_3") (pintype "input"))
      (node (ref "IC7") (pin "5") (pinfunction "IN_5") (pintype "input"))
      (node (ref "JP10") (pin "NO") (pinfunction "NO_NO") (pintype "passive"))
      (node (ref "L1") (pin "1") (pinfunction "1_1") (pintype "passive"))
      (node (ref "R24") (pin "1") (pinfunction "1_1") (pintype "passive"))
      (node (ref "X1") (pin "35") (pinfunction "1_35") (pintype "passive"))
      (node (ref "X1") (pin "36") (pinfunction "1_36") (pintype "passive"))
      (node (ref "X2") (pin "5") (pinfunction "1_5") (pintype "passive"))
      (node (ref "X2") (pin "6") (pinfunction "1_6") (pintype "passive"))
    )
    (net (code "4") (name "+12V") (class "Default")
      (node (ref "X1") (pin "37") (pinfunction "1_37") (pintype "passive"))
      (node (ref "X1") (pin "38") (pinfunction "1_38") (pintype "passive"))
      (node (ref "X2") (pin "3") (pinfunction "1_3") (pintype "passive"))
      (node (ref "X2") (pin "4") (pinfunction "1_4") (pintype "passive"))
    )
    (net (code "5") (name "+VAUX") (class "Default")
      (node (ref "JP5") (pin "2") (pinfunction "2_2") (pintype "passive"))
      (node (ref "X1") (pin "5") (pinfunction "1_5") (pintype "passive"))
      (node (ref "X2") (pin "10") (pinfunction "1_10") (pintype "passive"))
    )
    (net (code "12") (name "BOOT0") (class "Default")
      (node (ref "BOOT1") (pin "1") (pinfunction "1_1") (pintype "passive"))
      (node (ref "IC2") (pin "166") (pinfunction "BOOT0_166") (pintype "input"))
      (node (ref "R13") (pin "2") (pinfunction "2_2") (pintype "passive"))
      (node (ref "X2") (pin "2") (pinfunction "1_2") (pintype "passive"))
    )
    (net (code "13") (name "BYPASS_REG") (class "Default")
      (node (ref "IC2") (pin "48") (pinfunction "BYPASS_REG_48") (pintype "input"))
      (node (ref "R12") (pin "2") (pinfunction "2_2") (pintype "passive"))
    )
    (net (code "14") (name "DAC_OUT1") (class "Default")
      (node (ref "IC2") (pin "50") (pinfunction "PA4_50") (pintype "bidirectional"))
      (node (ref "Q2") (pin "1") (pinfunction "G_1") (pintype "passive"))
    )
    (net (code "15") (name "DIN2") (class "Default")
      (node (ref "IC2") (pin "8") (pinfunction "PC13_8") (pintype "bidirectional"))
      (node (ref "R9") (pin "2") (pinfunction "2_2") (pintype "passive"))
    )
    (net (code "16") (name "DOUT2") (class "Default")
      (node (ref "IC1") (pin "7") (pinfunction "I_7") (pintype "input"))
      (node (ref "IC1") (pin "9") (pinfunction "I_9") (pintype "input"))
      (node (ref "IC2") (pin "163") (pinfunction "PB5_163") (pintype "bidirectional"))
    )
    (net (code "17") (name "ENC_A") (class "Default")
      (node (ref "C5") (pin "2") (pinfunction "2_2") (pintype "passive"))
      (node (ref "IC2") (pin "119") (pinfunction "PC6_119") (pintype "bidirectional"))
      (node (ref "R2") (pin "1") (pinfunction "1_1") (pintype "passive"))
    )
    (net (code "18") (name "ENC_B") (class "Default")
      (node (ref "C6") (pin "1") (pinfunction "1_1") (pintype "passive"))
      (node (ref "IC2") (pin "120") (pinfunction "PC7_120") (pintype "bidirectional"))
      (node (ref "R10") (pin "1") (pinfunction "1_1") (pintype "passive"))
    )
    (net (code "19") (name "ENC_SW") (class "Default")
      (node (ref "C2") (pin "2") (pinfunction "2_2") (pintype "passive"))
      (node (ref "IC2") (pin "173") (pinfunction "PI4_173") (pintype "bidirectional"))
      (node (ref "SW2") (pin "E") (pinfunction "2_E") (pintype "passive"))
    )
    (net (code "20") (name "ETH_COL") (class "Default")
      (node (ref "IC2") (pin "47") (pinfunction "PA3_47") (pintype "bidirectional"))
      (node (ref "RN2") (pin "2") (pinfunction "1_2") (pintype "passive"))
    )
    (net (code "21") (name "ETH_CRS") (class "Default")
      (node (ref "IC2") (pin "40") (pinfunction "PA0_40") (pintype "bidirectional"))
      (node (ref "JP11") (pin "1") (pinfunction "1_1") (pintype "passive"))
      (node (ref "RN1") (pin "4") (pinfunction "1_4") (pintype "passive"))
    )
    (net (code "22") (name "ETH_MDC") (class "Default")
      (node (ref "IC13") (pin "31") (pinfunction "MDC_31") (pintype "input"))
      (node (ref "IC2") (pin "33") (pinfunction "PC1_33") (pintype "bidirectional"))
    )
    (net (code "23") (name "ETH_MDIO") (class "Default")
      (node (ref "IC13") (pin "30") (pinfunction "MDIO_30") (pintype "bidirectional"))
      (node (ref "IC2") (pin "42") (pinfunction "PA2_42") (pintype "bidirectional"))
      (node (ref "R32") (pin "1") (pinfunction "1_1") (pintype "passive"))
    )
    (net (code "24") (name "ETH_RXD0") (class "Default")
      (node (ref "IC2") (pin "54") (pinfunction "PC4_54") (pintype "bidirectional"))
      (node (ref "RN2") (pin "3") (pinfunction "1_3") (pintype "passive"))
    )
    (net (code "25") (name "ETH_RXD1") (class "Default")
      (node (ref "IC2") (pin "55") (pinfunction "PC5_55") (pintype "bidirectional"))
      (node (ref "RN2") (pin "4") (pinfunction "1_4") (pintype "passive"))
    )
    (net (code "26") (name "ETH_RXD2") (class "Default")
      (node (ref "IC2") (pin "83") (pinfunction "PH6_83") (pintype "bidirectional"))
      (node (ref "RN3") (pin "1") (pinfunction "1_1") (pintype "passive"))
    )
    (net (code "27") (name "ETH_RXD3") (class "Default")
      (node (ref "IC2") (pin "84") (pinfunction "PH7_84") (pintype "bidirectional"))
      (node (ref "RN3") (pin "2") (pinfunction "1_2") (pintype "passive"))
    )
    (net (code "28") (name "ETH_RX_CLK") (class "Default")
      (node (ref "IC2") (pin "41") (pinfunction "PA1_41") (pintype "bidirectional"))
      (node (ref "RN1") (pin "2") (pinfunction "1_2") (pintype "passive"))
    )
    (net (code "29") (name "ETH_RX_DV") (class "Default")
      (node (ref "IC2") (pin "53") (pinfunction "PA7_53") (pintype "bidirectional"))
      (node (ref "RN1") (pin "3") (pinfunction "1_3") (pintype "passive"))
    )
    (net (code "30") (name "ETH_RX_ERR") (class "Default")
      (node (ref "IC2") (pin "79") (pinfunction "PB10_79") (pintype "bidirectional"))
      (node (ref "JP14") (pin "2") (pinfunction "2_2") (pintype "passive"))
    )
    (net (code "31") (name "ETH_TXD0") (class "Default")
      (node (ref "IC2") (pin "85") (pinfunction "PB12_85") (pintype "bidirectional"))
      (node (ref "RN4") (pin "1") (pinfunction "1_1") (pintype "passive"))
    )
    (net (code "32") (name "ETH_TXD1") (class "Default")
      (node (ref "IC2") (pin "86") (pinfunction "PB13_86") (pintype "bidirectional"))
      (node (ref "RN4") (pin "2") (pinfunction "1_2") (pintype "passive"))
    )
    (net (code "33") (name "ETH_TXD2") (class "Default")
      (node (ref "IC2") (pin "34") (pinfunction "PC2_34") (pintype "bidirectional"))
      (node (ref "RN4") (pin "3") (pinfunction "1_3") (pintype "passive"))
    )
    (net (code "34") (name "ETH_TXD3") (class "Default")
      (node (ref "IC2") (pin "167") (pinfunction "PB8_167") (pintype "bidirectional"))
      (node (ref "RN4") (pin "4") (pinfunction "1_4") (pintype "passive"))
    )
    (net (code "35") (name "ETH_TX_CLK") (class "Default")
      (node (ref "IC2") (pin "35") (pinfunction "PC3_35") (pintype "bidirectional"))
      (node (ref "RN3") (pin "3") (pinfunction "1_3") (pintype "passive"))
    )
    (net (code "36") (name "ETH_TX_EN") (class "Default")
      (node (ref "IC2") (pin "80") (pinfunction "PB11_80") (pintype "bidirectional"))
      (node (ref "RN3") (pin "4") (pinfunction "1_4") (pintype "passive"))
    )
    (net (code "37") (name "FMC_A0") (class "Default")
      (node (ref "IC2") (pin "16") (pinfunction "PF0_16") (pintype "bidirectional"))
      (node (ref "IC5") (pin "23") (pinfunction "A0_23") (pintype "input"))
    )
    (net (code "38") (name "FMC_A1") (class "Default")
      (node (ref "IC2") (pin "17") (pinfunction "PF1_17") (pintype "bidirectional"))
      (node (ref "IC5") (pin "24") (pinfunction "A1_24") (pintype "input"))
    )
    (net (code "39") (name "FMC_A2") (class "Default")
      (node (ref "IC2") (pin "18") (pinfunction "PF2_18") (pintype "bidirectional"))
      (node (ref "IC5") (pin "25") (pinfunction "A2_25") (pintype "input"))
    )
    (net (code "40") (name "FMC_A3") (class "Default")
      (node (ref "IC2") (pin "19") (pinfunction "PF3_19") (pintype "bidirectional"))
      (node (ref "IC5") (pin "26") (pinfunction "A3_26") (pintype "input"))
    )
    (net (code "41") (name "FMC_A4") (class "Default")
      (node (ref "IC2") (pin "20") (pinfunction "PF4_20") (pintype "bidirectional"))
      (node (ref "IC5") (pin "29") (pinfunction "A4_29") (pintype "input"))
    )
    (net (code "42") (name "FMC_A5") (class "Default")
      (node (ref "IC2") (pin "21") (pinfunction "PF5_21") (pintype "bidirectional"))
      (node (ref "IC5") (pin "30") (pinfunction "A5_30") (pintype "input"))
    )
    (net (code "43") (name "FMC_A6") (class "Default")
      (node (ref "IC2") (pin "60") (pinfunction "PF12_60") (pintype "bidirectional"))
      (node (ref "IC5") (pin "31") (pinfunction "A6_31") (pintype "input"))
    )
    (net (code "44") (name "FMC_A7") (class "Default")
      (node (ref "IC2") (pin "63") (pinfunction "PF13_63") (pintype "bidirectional"))
      (node (ref "IC5") (pin "32") (pinfunction "A7_32") (pintype "input"))
    )
    (net (code "45") (name "FMC_A8") (class "Default")
      (node (ref "IC2") (pin "64") (pinfunction "PF14_64") (pintype "bidirectional"))
      (node (ref "IC5") (pin "33") (pinfunction "A8_33") (pintype "input"))
    )
    (net (code "46") (name "FMC_A9") (class "Default")
      (node (ref "IC2") (pin "65") (pinfunction "PF15_65") (pintype "bidirectional"))
      (node (ref "IC5") (pin "34") (pinfunction "A9_34") (pintype "input"))
    )
    (net (code "47") (name "FMC_A10") (class "Default")
      (node (ref "IC2") (pin "66") (pinfunction "PG0_66") (pintype "bidirectional"))
      (node (ref "IC5") (pin "22") (pinfunction "A10/AP_22") (pintype "input"))
    )
    (net (code "48") (name "FMC_A11") (class "Default")
      (node (ref "IC2") (pin "67") (pinfunction "PG1_67") (pintype "bidirectional"))
      (node (ref "IC5") (pin "35") (pinfunction "A11_35") (pintype "input"))
    )
    (net (code "49") (name "FMC_BA0") (class "Default")
      (node (ref "IC2") (pin "112") (pinfunction "PG4_112") (pintype "bidirectional"))
      (node (ref "IC5") (pin "20") (pinfunction "BA0_20") (pintype "input"))
    )
    (net (code "50") (name "FMC_BA1") (class "Default")
      (node (ref "IC2") (pin "113") (pinfunction "PG5_113") (pintype "bidirectional"))
      (node (ref "IC5") (pin "21") (pinfunction "BA1_21") (pintype "input"))
    )
    (net (code "51") (name "FMC_D0") (class "Default")
      (node (ref "IC2") (pin "97") (pinfunction "PD14_97") (pintype "bidirectional"))
      (node (ref "IC5") (pin "2") (pinfunction "DQ0_2") (pintype "bidirectional"))
    )
    (net (code "52") (name "FMC_D1") (class "Default")
      (node (ref "IC2") (pin "98") (pinfunction "PD15_98") (pintype "bidirectional"))
      (node (ref "IC5") (pin "4") (pinfunction "DQ1_4") (pintype "bidirectional"))
    )
    (net (code "53") (name "FMC_D2") (class "Default")
      (node (ref "IC2") (pin "142") (pinfunction "PD0_142") (pintype "bidirectional"))
      (node (ref "IC5") (pin "5") (pinfunction "DQ2_5") (pintype "bidirectional"))
    )
    (net (code "54") (name "FMC_D3") (class "Default")
      (node (ref "IC2") (pin "143") (pinfunction "PD1_143") (pintype "bidirectional"))
      (node (ref "IC5") (pin "7") (pinfunction "DQ3_7") (pintype "bidirectional"))
    )
    (net (code "55") (name "FMC_D4") (class "Default")
      (node (ref "IC2") (pin "68") (pinfunction "PE7_68") (pintype "bidirectional"))
      (node (ref "IC5") (pin "8") (pinfunction "DQ4_8") (pintype "bidirectional"))
    )
    (net (code "56") (name "FMC_D5") (class "Default")
      (node (ref "IC2") (pin "69") (pinfunction "PE8_69") (pintype "bidirectional"))
      (node (ref "IC5") (pin "10") (pinfunction "DQ5_10") (pintype "bidirectional"))
    )
    (net (code "57") (name "FMC_D6") (class "Default")
      (node (ref "IC2") (pin "70") (pinfunction "PE9_70") (pintype "bidirectional"))
      (node (ref "IC5") (pin "11") (pinfunction "DQ6_11") (pintype "bidirectional"))
    )
    (net (code "58") (name "FMC_D7") (class "Default")
      (node (ref "IC2") (pin "73") (pinfunction "PE10_73") (pintype "bidirectional"))
      (node (ref "IC5") (pin "13") (pinfunction "DQ7_13") (pintype "bidirectional"))
    )
    (net (code "59") (name "FMC_D8") (class "Default")
      (node (ref "IC2") (pin "74") (pinfunction "PE11_74") (pintype "bidirectional"))
      (node (ref "IC5") (pin "42") (pinfunction "DQ8_42") (pintype "bidirectional"))
    )
    (net (code "60") (name "FMC_D9") (class "Default")
      (node (ref "IC2") (pin "75") (pinfunction "PE12_75") (pintype "bidirectional"))
      (node (ref "IC5") (pin "44") (pinfunction "DQ9_44") (pintype "bidirectional"))
    )
    (net (code "61") (name "FMC_D10") (class "Default")
      (node (ref "IC2") (pin "76") (pinfunction "PE13_76") (pintype "bidirectional"))
      (node (ref "IC5") (pin "45") (pinfunction "DQ10_45") (pintype "bidirectional"))
    )
    (net (code "62") (name "FMC_D11") (class "Default")
      (node (ref "IC2") (pin "77") (pinfunction "PE14_77") (pintype "bidirectional"))
      (node (ref "IC5") (pin "47") (pinfunction "DQ11_47") (pintype "bidirectional"))
    )
    (net (code "63") (name "FMC_D12") (class "Default")
      (node (ref "IC2") (pin "78") (pinfunction "PE15_78") (pintype "bidirectional"))
      (node (ref "IC5") (pin "48") (pinfunction "DQ12_48") (pintype "bidirectional"))
    )
    (net (code "64") (name "FMC_D13") (class "Default")
      (node (ref "IC2") (pin "89") (pinfunction "PD8_89") (pintype "bidirectional"))
      (node (ref "IC5") (pin "50") (pinfunction "DQ13_50") (pintype "bidirectional"))
    )
    (net (code "65") (name "FMC_D14") (class "Default")
      (node (ref "IC2") (pin "90") (pinfunction "PD9_90") (pintype "bidirectional"))
      (node (ref "IC5") (pin "51") (pinfunction "DQ14_51") (pintype "bidirectional"))
    )
    (net (code "66") (name "FMC_D15") (class "Default")
      (node (ref "IC2") (pin "91") (pinfunction "PD10_91") (pintype "bidirectional"))
      (node (ref "IC5") (pin "53") (pinfunction "DQ15_53") (pintype "bidirectional"))
    )
    (net (code "67") (name "FMC_NBL0") (class "Default")
      (node (ref "IC2") (pin "169") (pinfunction "PE0_169") (pintype "bidirectional"))
      (node (ref "IC5") (pin "15") (pinfunction "LDQM_15") (pintype "input"))
    )
    (net (code "68") (name "FMC_NBL1") (class "Default")
      (node (ref "IC2") (pin "170") (pinfunction "PE1_170") (pintype "bidirectional"))
      (node (ref "IC5") (pin "39") (pinfunction "UDQM_39") (pintype "input"))
    )
    (net (code "69") (name "FMC_SDCKE0") (class "Default")
      (node (ref "IC2") (pin "43") (pinfunction "PH2_43") (pintype "bidirectional"))
      (node (ref "IC5") (pin "37") (pinfunction "CKE_37") (pintype "input"))
    )
    (net (code "70") (name "FMC_SDCLK") (class "Default")
      (node (ref "IC2") (pin "116") (pinfunction "PG8_116") (pintype "bidirectional"))
      (node (ref "IC5") (pin "38") (pinfunction "CLK_38") (pintype "input"))
    )
    (net (code "71") (name "FMC_SDNCAS") (class "Default")
      (node (ref "IC2") (pin "160") (pinfunction "PG15_160") (pintype "bidirectional"))
      (node (ref "IC5") (pin "17") (pinfunction "~{CAS}_17") (pintype "input"))
    )
    (net (code "72") (name "FMC_SDNE0") (class "Default")
      (node (ref "IC2") (pin "44") (pinfunction "PH3_44") (pintype "bidirectional"))
      (node (ref "IC5") (pin "19") (pinfunction "~{CS}_19") (pintype "input"))
      (node (ref "R23") (pin "2") (pinfunction "2_2") (pintype "passive"))
    )
    (net (code "73") (name "FMC_SDNRAS") (class "Default")
      (node (ref "IC2") (pin "59") (pinfunction "PF11_59") (pintype "bidirectional"))
      (node (ref "IC5") (pin "18") (pinfunction "~{RAS}_18") (pintype "input"))
    )
    (net (code "74") (name "FMC_SDNWE") (class "Default")
      (node (ref "IC2") (pin "46") (pinfunction "PH5_46") (pintype "bidirectional"))
      (node (ref "IC5") (pin "16") (pinfunction "~{WE}_16") (pintype "input"))
    )
    (net (code "75") (name "GND") (class "Default")
      (node (ref "B1") (pin "2") (pinfunction "-_2") (pintype "passive"))
      (node (ref "C1") (pin "2") (pinfunction "2_2") (pintype "passive"))
      (node (ref "C10") (pin "2") (pinfunction "2_2") (pintype "passive"))
      (node (ref "C11") (pin "2") (pinfunction "-_2") (pintype "passive"))
      (node (ref "C12") (pin "2") (pinfunction "2_2") (pintype "passive"))
      (node (ref "C13") (pin "-") (pinfunction "-_-") (pintype "passive"))
      (node (ref "C14") (pin "2") (pinfunction "2_2") (pintype "passive"))
      (node (ref "C15") (pin "2") (pinfunction "2_2") (pintype "passive"))
      (node (ref "C16") (pin "2") (pinfunction "2_2") (pintype "passive"))
      (node (ref "C17") (pin "2") (pinfunction "2_2") (pintype "passive"))
      (node (ref "C18") (pin "2") (pinfunction "2_2") (pintype "passive"))
      (node (ref "C19") (pin "2") (pinfunction "2_2") (pintype "passive"))
      (node (ref "C2") (pin "1") (pinfunction "1_1") (pintype "passive"))
      (node (ref "C20") (pin "-") (pinfunction "-_-") (pintype "passive"))
      (node (ref "C21") (pin "2") (pinfunction "2_2") (pintype "passive"))
      (node (ref "C22") (pin "2") (pinfunction "2_2") (pintype "passive"))
      (node (ref "C23") (pin "2") (pinfunction "2_2") (pintype "passive"))
      (node (ref "C24") (pin "2") (pinfunction "2_2") (pintype "passive"))
      (node (ref "C25") (pin "2") (pinfunction "2_2") (pintype "passive"))
      (node (ref "C26") (pin "2") (pinfunction "2_2") (pintype "passive"))
      (node (ref "C27") (pin "2") (pinfunction "2_2") (pintype "passive"))
      (node (ref "C28") (pin "2") (pinfunction "2_2") (pintype "passive"))
      (node (ref "C29") (pin "2") (pinfunction "2_2") (pintype "passive"))
      (node (ref "C3") (pin "1") (pinfunction "1_1") (pintype "passive"))
      (node (ref "C30") (pin "2") (pinfunction "2_2") (pintype "passive"))
      (node (ref "C31") (pin "2") (pinfunction "2_2") (pintype "passive"))
      (node (ref "C32") (pin "2") (pinfunction "2_2") (pintype "passive"))
      (node (ref "C33") (pin "2") (pinfunction "2_2") (pintype "passive"))
      (node (ref "C34") (pin "2") (pinfunction "2_2") (pintype "passive"))
      (node (ref "C35") (pin "2") (pinfunction "2_2") (pintype "passive"))
      (node (ref "C36") (pin "2") (pinfunction "2_2") (pintype "passive"))
      (node (ref "C37") (pin "2") (pinfunction "2_2") (pintype "passive"))
      (node (ref "C38") (pin "1") (pinfunction "1_1") (pintype "passive"))
      (node (ref "C39") (pin "2") (pinfunction "2_2") (pintype "passive"))
      (node (ref "C4") (pin "2") (pinfunction "2_2") (pintype "passive"))
      (node (ref "C40") (pin "2") (pinfunction "2_2") (pintype "passive"))
      (node (ref "C41") (pin "2") (pinfunction "2_2") (pintype "passive"))
      (node (ref "C42") (pin "2") (pinfunction "2_2") (pintype "passive"))
      (node (ref "C43") (pin "2") (pinfunction "2_2") (pintype "passive"))
      (node (ref "C44") (pin "2") (pinfunction "2_2") (pintype "passive"))
      (node (ref "C45") (pin "2") (pinfunction "2_2") (pintype "passive"))
      (node (ref "C46") (pin "2") (pinfunction "2_2") (pintype "passive"))
      (node (ref "C47") (pin "-") (pinfunction "-_-") (pintype "passive"))
      (node (ref "C48") (pin "2") (pinfunction "2_2") (pintype "passive"))
      (node (ref "C49") (pin "2") (pinfunction "2_2") (pintype "passive"))
      (node (ref "C5") (pin "1") (pinfunction "1_1") (pintype "passive"))
      (node (ref "C50") (pin "1") (pinfunction "1_1") (pintype "passive"))
      (node (ref "C51") (pin "1") (pinfunction "1_1") (pintype "passive"))
      (node (ref "C52") (pin "1") (pinfunction "1_1") (pintype "passive"))
      (node (ref "C53") (pin "1") (pinfunction "1_1") (pintype "passive"))
      (node (ref "C54") (pin "1") (pinfunction "1_1") (pintype "passive"))
      (node (ref "C55") (pin "2") (pinfunction "2_2") (pintype "passive"))
      (node (ref "C56") (pin "2") (pinfunction "2_2") (pintype "passive"))
      (node (ref "C57") (pin "1") (pinfunction "1_1") (pintype "passive"))
      (node (ref "C58") (pin "2") (pinfunction "2_2") (pintype "passive"))
      (node (ref "C59") (pin "1") (pinfunction "1_1") (pintype "passive"))
      (node (ref "C6") (pin "2") (pinfunction "2_2") (pintype "passive"))
      (node (ref "C60") (pin "2") (pinfunction "2_2") (pintype "passive"))
      (node (ref "C61") (pin "2") (pinfunction "2_2") (pintype "passive"))
      (node (ref "C62") (pin "-") (pinfunction "-_-") (pintype "passive"))
      (node (ref "C63") (pin "2") (pinfunction "2_2") (pintype "passive"))
      (node (ref "C64") (pin "2") (pinfunction "2_2") (pintype "passive"))
      (node (ref "C65") (pin "2") (pinfunction "2_2") (pintype "passive"))
      (node (ref "C66") (pin "2") (pinfunction "2_2") (pintype "passive"))
      (node (ref "C67") (pin "2") (pinfunction "2_2") (pintype "passive"))
      (node (ref "C7") (pin "1") (pinfunction "1_1") (pintype "passive"))
      (node (ref "C8") (pin "2") (pinfunction "2_2") (pintype "passive"))
      (node (ref "C9") (pin "1") (pinfunction "1_1") (pintype "passive"))
      (node (ref "D1") (pin "A") (pinfunction "A_A") (pintype "passive"))
      (node (ref "IC1") (pin "8") (pinfunction "VSS_8") (pintype "power_in"))
      (node (ref "IC10") (pin "3") (pinfunction "GND_3") (pintype "power_in"))
      (node (ref "IC11") (pin "13") (pinfunction "A1_13") (pintype "input"))
      (node (ref "IC11") (pin "14") (pinfunction "A0_14") (pintype "input"))
      (node (ref "IC11") (pin "6") (pinfunction "GND_6") (pintype "passive"))
      (node (ref "IC12") (pin "3") (pinfunction "GND_3") (pintype "power_in"))
      (node (ref "IC13") (pin "15") (pinfunction "AGND-15_15") (pintype "power_in"))
      (node (ref "IC13") (pin "19") (pinfunction "AGND-19_19") (pintype "power_in"))
      (node (ref "IC13") (pin "35") (pinfunction "IOGND-35_35") (pintype "power_in"))
      (node (ref "IC13") (pin "36") (pinfunction "DGND_36") (pintype "power_in"))
      (node (ref "IC13") (pin "47") (pinfunction "IOGND-47_47") (pintype "power_in"))
      (node (ref "IC14") (pin "3") (pinfunction "GND_3") (pintype "power_in"))
      (node (ref "IC2") (pin "103") (pinfunction "VSSDSI_2_103") (pintype "power_in"))
      (node (ref "IC2") (pin "109") (pinfunction "VSSDSI_109") (pintype "power_in"))
      (node (ref "IC2") (pin "117") (pinfunction "VSS_7_117") (pintype "power_in"))
      (node (ref "IC2") (pin "130") (pinfunction "VSS_8_130") (pintype "power_in"))
      (node (ref "IC2") (pin "135") (pinfunction "VSS_9_135") (pintype "power_in"))
      (node (ref "IC2") (pin "14") (pinfunction "VSS_2_14") (pintype "power_in"))
      (node (ref "IC2") (pin "148") (pinfunction "VSS_10_148") (pintype "power_in"))
      (node (ref "IC2") (pin "158") (pinfunction "VSS_158") (pintype "power_in"))
      (node (ref "IC2") (pin "22") (pinfunction "VSS_3_22") (pintype "power_in"))
      (node (ref "IC2") (pin "37") (pinfunction "VSSA_37") (pintype "power_in"))
      (node (ref "IC2") (pin "61") (pinfunction "VSS_4_61") (pintype "power_in"))
      (node (ref "IC2") (pin "71") (pinfunction "VSS_5_71") (pintype "power_in"))
      (node (ref "IC2") (pin "95") (pinfunction "VSS_6_95") (pintype "power_in"))
      (node (ref "IC3") (pin "1") (pinfunction "ADJ_1") (pintype "input"))
      (node (ref "IC4") (pin "3") (pinfunction "GND_3") (pintype "power_in"))
      (node (ref "IC5") (pin "12") (pinfunction "GNDQ-12_12") (pintype "power_in"))
      (node (ref "IC5") (pin "28") (pinfunction "GND-28_28") (pintype "power_in"))
      (node (ref "IC5") (pin "41") (pinfunction "GND_41") (pintype "power_in"))
      (node (ref "IC5") (pin "46") (pinfunction "GNDQ-46_46") (pintype "power_in"))
      (node (ref "IC5") (pin "52") (pinfunction "GNDQ-52_52") (pintype "power_in"))
      (node (ref "IC5") (pin "54") (pinfunction "GND-54_54") (pintype "power_in"))
      (node (ref "IC5") (pin "6") (pinfunction "GNDQ-6_6") (pintype "power_in"))
      (node (ref "IC6") (pin "1") (pinfunction "A0_1") (pintype "input"))
      (node (ref "IC6") (pin "2") (pinfunction "A1_2") (pintype "input"))
      (node (ref "IC6") (pin "3") (pinfunction "A2_3") (pintype "input"))
      (node (ref "IC6") (pin "4") (pinfunction "GND_4") (pintype "passive"))
      (node (ref "IC6") (pin "7") (pinfunction "WP_7") (pintype "input"))
      (node (ref "IC7") (pin "2") (pinfunction "GND_2") (pintype "power_in"))
      (node (ref "IC8") (pin "2") (pinfunction "GND_2") (pintype "power_in"))
      (node (ref "IC9") (pin "3") (pinfunction "GND_3") (pintype "power_in"))
      (node (ref "J1") (pin "6") (pinfunction "VSS_6") (pintype "power_in"))
      (node (ref "J1") (pin "S") (pinfunction "SH_S") (pintype "passive"))
      (node (ref "J1") (pin "S1") (pinfunction "SH_S1") (pintype "passive"))
      (node (ref "J1") (pin "S2") (pinfunction "SH_S2") (pintype "passive"))
      (node (ref "J1") (pin "SW2") (pinfunction "SW2_SW2") (pintype "passive"))
      (node (ref "J2") (pin "5") (pinfunction "GND_5") (pintype "passive"))
      (node (ref "JP1") (pin "1") (pinfunction "1_1") (pintype "passive"))
      (node (ref "JP8") (pin "NC") (pinfunction "NC_NC") (pintype "passive"))
      (node (ref "JP9") (pin "NC") (pinfunction "NC_NC") (pintype "passive"))
      (node (ref "LCD1") (pin "29") (pinfunction "GND-29_29") (pintype "power_in"))
      (node (ref "LCD1") (pin "3") (pinfunction "GND-3_3") (pintype "power_in"))
      (node (ref "Q1") (pin "E") (pinfunction "E_E") (pintype "passive"))
      (node (ref "Q2") (pin "2") (pinfunction "S_2") (pintype "passive"))
      (node (ref "R12") (pin "1") (pinfunction "1_1") (pintype "passive"))
      (node (ref "R13") (pin "1") (pinfunction "1_1") (pintype "passive"))
      (node (ref "R18") (pin "1") (pinfunction "1_1") (pintype "passive"))
      (node (ref "R26") (pin "2") (pinfunction "2_2") (pintype "passive"))
      (node (ref "R35") (pin "1") (pinfunction "1_1") (pintype "passive"))
      (node (ref "R38") (pin "1") (pinfunction "1_1") (pintype "passive"))
      (node (ref "R48") (pin "1") (pinfunction "1_1") (pintype "passive"))
      (node (ref "SW1") (pin "2") (pinfunction "2_2") (pintype "passive"))
      (node (ref "SW2") (pin "C") (pinfunction "C_C") (pintype "passive"))
      (node (ref "SW2") (pin "D") (pinfunction "1_D") (pintype "passive"))
      (node (ref "SW2") (pin "GND1") (pinfunction "C_GND1") (pintype "passive"))
      (node (ref "SW2") (pin "GND2") (pinfunction "C_GND2") (pintype "passive"))
      (node (ref "TP1") (pin "1") (pinfunction "P$1_1") (pintype "bidirectional"))
      (node (ref "X1") (pin "1") (pinfunction "1_1") (pintype "passive"))
      (node (ref "X1") (pin "15") (pinfunction "1_15") (pintype "passive"))
      (node (ref "X1") (pin "16") (pinfunction "1_16") (pintype "passive"))
      (node (ref "X1") (pin "2") (pinfunction "1_2") (pintype "passive"))
      (node (ref "X1") (pin "29") (pinfunction "1_29") (pintype "passive"))
      (node (ref "X1") (pin "30") (pinfunction "1_30") (pintype "passive"))
      (node (ref "X1") (pin "34") (pinfunction "1_34") (pintype "passive"))
      (node (ref "X1") (pin "39") (pinfunction "1_39") (pintype "passive"))
      (node (ref "X1") (pin "40") (pinfunction "1_40") (pintype "passive"))
      (node (ref "X2") (pin "7") (pinfunction "1_7") (pintype "passive"))
      (node (ref "X2") (pin "8") (pinfunction "1_8") (pintype "passive"))
      (node (ref "X2") (pin "9") (pinfunction "1_9") (pintype "passive"))
      (node (ref "X3") (pin "3") (pinfunction "1_3") (pintype "passive"))
      (node (ref "X4") (pin "3") (pinfunction "S_3") (pintype "passive"))
      (node (ref "X5") (pin "4") (pinfunction "GND_4") (pintype "passive"))
      (node (ref "X5") (pin "5") (pinfunction "GND_5") (pintype "passive"))
    )
    (net (code "76") (name "I2C1_SCL") (class "Default")
      (node (ref "IC11") (pin "12") (pinfunction "SCL_12") (pintype "bidirectional"))
      (node (ref "IC2") (pin "164") (pinfunction "PB6_164") (pintype "bidirectional"))
      (node (ref "IC6") (pin "6") (pinfunction "SCL_6") (pintype "bidirectional"))
      (node (ref "R15") (pin "2") (pinfunction "2_2") (pintype "passive"))
      (node (ref "SCL") (pin "1") (pinfunction "1_1") (pintype "passive"))
      (node (ref "X1") (pin "12") (pinfunction "1_12") (pintype "passive"))
    )
    (net (code "77") (name "I2C1_SDA") (class "Default")
      (node (ref "IC11") (pin "11") (pinfunction "SDA_11") (pintype "bidirectional"))
      (node (ref "IC2") (pin "165") (pinfunction "PB7_165") (pintype "bidirectional"))
      (node (ref "IC6") (pin "5") (pinfunction "SDA_5") (pintype "bidirectional"))
      (node (ref "R16") (pin "2") (pinfunction "2_2") (pintype "passive"))
      (node (ref "SDA") (pin "2") (pinfunction "2_2") (pintype "passive"))
      (node (ref "X1") (pin "14") (pinfunction "1_14") (pintype "passive"))
    )
    (net (code "78") (name "IRQ_TOUCH") (class "Default")
      (node (ref "IC11") (pin "10") (pinfunction "~{PENIRQ}_10") (pintype "output"))
      (node (ref "IC2") (pin "151") (pinfunction "PD7_151") (pintype "bidirectional"))
    )
    (net (code "79") (name "LCD_DISP") (class "Default")
      (node (ref "LCD1") (pin "31") (pinfunction "DISP_31") (pintype "input"))
      (node (ref "R31") (pin "1") (pinfunction "1_1") (pintype "passive"))
    )
    (net (code "80") (name "LED_ACT") (class "Default")
      (node (ref "IC13") (pin "26") (pinfunction "AN_EN(LED_ACT/COL)_26") (pintype "output"))
      (node (ref "R36") (pin "2") (pinfunction "2_2") (pintype "passive"))
      (node (ref "R44") (pin "2") (pinfunction "2_2") (pintype "passive"))
    )
    (net (code "81") (name "LED_LINK") (class "Default")
      (node (ref "IC13") (pin "28") (pinfunction "AN_0(LED_LINK)_28") (pintype "output"))
      (node (ref "R43") (pin "2") (pinfunction "2_2") (pintype "passive"))
      (node (ref "R45") (pin "2") (pinfunction "2_2") (pintype "passive"))
    )
    (net (code "82") (name "LED_SPEED") (class "Default")
      (node (ref "IC13") (pin "27") (pinfunction "AN_1(LED_SPEED)_27") (pintype "output"))
      (node (ref "R41") (pin "2") (pinfunction "2_2") (pintype "passive"))
      (node (ref "SPEED") (pin "C") (pinfunction "C_C") (pintype "passive"))
    )
    (net (code "83") (name "LTDC_B2") (class "Default")
      (node (ref "IC2") (pin "150") (pinfunction "PD6_150") (pintype "bidirectional"))
      (node (ref "LCD1") (pin "23") (pinfunction "B2_23") (pintype "input"))
    )
    (net (code "84") (name "LTDC_B3") (class "Default")
      (node (ref "IC2") (pin "154") (pinfunction "PG11_154") (pintype "bidirectional"))
      (node (ref "LCD1") (pin "24") (pinfunction "B3_24") (pintype "input"))
    )
    (net (code "85") (name "LTDC_B4") (class "Default")
      (node (ref "IC2") (pin "155") (pinfunction "PG12_155") (pintype "bidirectional"))
      (node (ref "LCD1") (pin "25") (pinfunction "B4_25") (pintype "input"))
    )
    (net (code "86") (name "LTDC_B5") (class "Default")
      (node (ref "IC2") (pin "174") (pinfunction "PI5_174") (pintype "bidirectional"))
      (node (ref "LCD1") (pin "26") (pinfunction "B5_26") (pintype "input"))
    )
    (net (code "87") (name "LTDC_B6") (class "Default")
      (node (ref "IC2") (pin "175") (pinfunction "PI6_175") (pintype "bidirectional"))
      (node (ref "LCD1") (pin "27") (pinfunction "B6_27") (pintype "input"))
    )
    (net (code "88") (name "LTDC_B7") (class "Default")
      (node (ref "IC2") (pin "176") (pinfunction "PI7_176") (pintype "bidirectional"))
      (node (ref "LCD1") (pin "28") (pinfunction "B7_28") (pintype "input"))
    )
    (net (code "89") (name "LTDC_CLK") (class "Default")
      (node (ref "IC2") (pin "115") (pinfunction "PG7_115") (pintype "bidirectional"))
      (node (ref "LCD1") (pin "30") (pinfunction "CLK_30") (pintype "input"))
    )
    (net (code "90") (name "LTDC_DE") (class "Default")
      (node (ref "IC2") (pin "28") (pinfunction "PF10_28") (pintype "bidirectional"))
      (node (ref "LCD1") (pin "34") (pinfunction "DE/NC2_34") (pintype "passive"))
    )
    (net (code "91") (name "LTDC_G2") (class "Default")
      (node (ref "IC2") (pin "52") (pinfunction "PA6_52") (pintype "bidirectional"))
      (node (ref "LCD1") (pin "15") (pinfunction "G2_15") (pintype "input"))
    )
    (net (code "92") (name "LTDC_G3") (class "Default")
      (node (ref "IC2") (pin "153") (pinfunction "PG10_153") (pintype "bidirectional"))
      (node (ref "LCD1") (pin "16") (pinfunction "G3_16") (pintype "input"))
    )
    (net (code "93") (name "LTDC_G4") (class "Default")
      (node (ref "IC2") (pin "45") (pinfunction "PH4_45") (pintype "bidirectional"))
      (node (ref "LCD1") (pin "17") (pinfunction "G4_17") (pintype "input"))
    )
    (net (code "94") (name "LTDC_G5") (class "Default")
      (node (ref "IC2") (pin "132") (pinfunction "PI0_132") (pintype "bidirectional"))
      (node (ref "LCD1") (pin "18") (pinfunction "G5_18") (pintype "input"))
    )
    (net (code "95") (name "LTDC_G6") (class "Default")
      (node (ref "IC2") (pin "13") (pinfunction "PI11_13") (pintype "bidirectional"))
      (node (ref "LCD1") (pin "19") (pinfunction "G6_19") (pintype "input"))
    )
    (net (code "96") (name "LTDC_G7") (class "Default")
      (node (ref "IC2") (pin "145") (pinfunction "PD3_145") (pintype "bidirectional"))
      (node (ref "LCD1") (pin "20") (pinfunction "G7_20") (pintype "input"))
    )
    (net (code "97") (name "LTDC_HSYNC") (class "Default")
      (node (ref "IC2") (pin "12") (pinfunction "PI10_12") (pintype "bidirectional"))
      (node (ref "LCD1") (pin "32") (pinfunction "HSYNC_32") (pintype "input"))
    )
    (net (code "98") (name "LTDC_R2") (class "Default")
      (node (ref "IC2") (pin "139") (pinfunction "PC10_139") (pintype "bidirectional"))
      (node (ref "LCD1") (pin "7") (pinfunction "R2_7") (pintype "input"))
    )
    (net (code "99") (name "LTDC_R3") (class "Default")
      (node (ref "IC2") (pin "56") (pinfunction "PB0_56") (pintype "bidirectional"))
      (node (ref "LCD1") (pin "8") (pinfunction "R3_8") (pintype "input"))
    )
    (net (code "100") (name "LTDC_R4") (class "Default")
      (node (ref "IC2") (pin "51") (pinfunction "PA5_51") (pintype "bidirectional"))
      (node (ref "LCD1") (pin "9") (pinfunction "R4_9") (pintype "input"))
    )
    (net (code "101") (name "LTDC_R5") (class "Default")
      (node (ref "IC2") (pin "32") (pinfunction "PC0_32") (pintype "bidirectional"))
      (node (ref "LCD1") (pin "10") (pinfunction "R5_10") (pintype "input"))
    )
    (net (code "102") (name "LTDC_R6") (class "Default")
      (node (ref "IC2") (pin "57") (pinfunction "PB1_57") (pintype "bidirectional"))
      (node (ref "LCD1") (pin "11") (pinfunction "R6_11") (pintype "input"))
    )
    (net (code "103") (name "LTDC_R7") (class "Default")
      (node (ref "IC2") (pin "114") (pinfunction "PG6_114") (pintype "bidirectional"))
      (node (ref "LCD1") (pin "12") (pinfunction "R7_12") (pintype "input"))
    )
    (net (code "104") (name "LTDC_VSYNC") (class "Default")
      (node (ref "IC2") (pin "11") (pinfunction "PI9_11") (pintype "bidirectional"))
      (node (ref "LCD1") (pin "33") (pinfunction "VSYNC_33") (pintype "input"))
    )
    (net (code "105") (name "MCLK_25") (class "Default")
      (node (ref "IC2") (pin "122") (pinfunction "PC9_122") (pintype "bidirectional"))
      (node (ref "RN1") (pin "1") (pinfunction "1_1") (pintype "passive"))
    )
    (net (code "106") (name "Net-(B1-+-Pad1)") (class "Default")
      (node (ref "B1") (pin "1") (pinfunction "+_1") (pintype "passive"))
      (node (ref "B1") (pin "3") (pinfunction "+_3") (pintype "passive"))
      (node (ref "JP5") (pin "1") (pinfunction "1_1") (pintype "passive"))
      (node (ref "JP6") (pin "NC") (pinfunction "NC_NC") (pintype "passive"))
    )
    (net (code "107") (name "Net-(C51-Pad2)") (class "Default")
      (node (ref "C51") (pin "2") (pinfunction "2_2") (pintype "passive"))
      (node (ref "JP10") (pin "COM") (pinfunction "COM_COM") (pintype "passive"))
      (node (ref "SP1") (pin "+B") (pinfunction "+_+B") (pintype "passive"))
      (node (ref "SP1") (pin "+B.1") (pinfunction "+_+B.1") (pintype "passive"))
    )
    (net (code "108") (name "Net-(C56-Pad1)") (class "Default")
      (node (ref "C56") (pin "1") (pinfunction "1_1") (pintype "passive"))
      (node (ref "R33") (pin "1") (pinfunction "1_1") (pintype "passive"))
      (node (ref "R34") (pin "2") (pinfunction "2_2") (pintype "passive"))
    )
    (net (code "109") (name "Net-(C58-Pad1)") (class "Default")
      (node (ref "C58") (pin "1") (pinfunction "1_1") (pintype "passive"))
      (node (ref "R37") (pin "1") (pinfunction "1_1") (pintype "passive"))
      (node (ref "R42") (pin "2") (pinfunction "2_2") (pintype "passive"))
    )
    (net (code "110") (name "Net-(IC1A-I)") (class "Default")
      (node (ref "IC1") (pin "3") (pinfunction "I_3") (pintype "input"))
      (node (ref "R8") (pin "2") (pinfunction "2_2") (pintype "passive"))
    )
    (net (code "111") (name "Net-(IC1A-O)") (class "Default")
      (node (ref "IC1") (pin "2") (pinfunction "O_2") (pintype "output"))
      (node (ref "R9") (pin "1") (pinfunction "1_1") (pintype "passive"))
    )
    (net (code "112") (name "Net-(IC1F-I)") (class "Default")
      (node (ref "IC1") (pin "14") (pinfunction "I_14") (pintype "input"))
      (node (ref "R4") (pin "2") (pinfunction "2_2") (pintype "passive"))
    )
    (net (code "113") (name "Net-(IC1F-O)") (class "Default")
      (node (ref "IC1") (pin "15") (pinfunction "O_15") (pintype "output"))
      (node (ref "R5") (pin "1") (pinfunction "1_1") (pintype "passive"))
    )
    (net (code "114") (name "Net-(IC2D-VCAPDSI)") (class "Default")
      (node (ref "IC2") (pin "100") (pinfunction "VCAPDSI_100") (pintype "power_in"))
      (node (ref "IC2") (pin "106") (pinfunction "VDD12DSI_106") (pintype "power_in"))
    )
    (net (code "115") (name "Net-(IC8-SW)") (class "Default")
      (node (ref "D2") (pin "A") (pinfunction "A_A") (pintype "passive"))
      (node (ref "IC8") (pin "1") (pinfunction "SW_1") (pintype "output"))
      (node (ref "L1") (pin "2") (pinfunction "2_2") (pintype "passive"))
    )
    (net (code "116") (name "Net-(IC8-VIN)") (class "Default")
      (node (ref "IC8") (pin "5") (pinfunction "VIN_5") (pintype "input"))
      (node (ref "R24") (pin "2") (pinfunction "2_2") (pintype "passive"))
    )
    (net (code "117") (name "Net-(IC12-IO1)") (class "Default")
      (node (ref "IC12") (pin "1") (pinfunction "IO1_1") (pintype "bidirectional"))
      (node (ref "IC13") (pin "17") (pinfunction "TD+_17") (pintype "bidirectional"))
      (node (ref "R33") (pin "2") (pinfunction "2_2") (pintype "passive"))
      (node (ref "X5") (pin "1") (pinfunction "TD+_1") (pintype "input"))
    )
    (net (code "118") (name "Net-(IC12-IO2)") (class "Default")
      (node (ref "IC12") (pin "2") (pinfunction "IO2_2") (pintype "bidirectional"))
      (node (ref "IC13") (pin "16") (pinfunction "TD-_16") (pintype "bidirectional"))
      (node (ref "R34") (pin "1") (pinfunction "1_1") (pintype "passive"))
      (node (ref "X5") (pin "2") (pinfunction "TD-_2") (pintype "input"))
    )
    (net (code "119") (name "Net-(IC12-IO3)") (class "Default")
      (node (ref "IC12") (pin "4") (pinfunction "IO3_4") (pintype "bidirectional"))
      (node (ref "IC13") (pin "14") (pinfunction "RD+_14") (pintype "bidirectional"))
      (node (ref "R37") (pin "2") (pinfunction "2_2") (pintype "passive"))
      (node (ref "X5") (pin "7") (pinfunction "RD+_7") (pintype "input"))
    )
    (net (code "120") (name "Net-(IC12-IO4)") (class "Default")
      (node (ref "IC12") (pin "5") (pinfunction "IO4_5") (pintype "bidirectional"))
      (node (ref "IC13") (pin "13") (pinfunction "RD-_13") (pintype "bidirectional"))
      (node (ref "R42") (pin "1") (pinfunction "1_1") (pintype "passive"))
      (node (ref "X5") (pin "8") (pinfunction "RD-_8") (pintype "input"))
    )
    (net (code "121") (name "Net-(IC13-CRS{slash}CRS_DV{slash}LED_CFG)") (class "Default")
      (node (ref "IC13") (pin "40") (pinfunction "CRS/CRS_DV/LED_CFG_40") (pintype "output"))
      (node (ref "RN1") (pin "5") (pinfunction "2_5") (pintype "passive"))
    )
    (net (code "122") (name "Net-(IC13-MDIX_EN(RX_ER))") (class "Default")
      (node (ref "IC13") (pin "41") (pinfunction "MDIX_EN(RX_ER)_41") (pintype "output"))
      (node (ref "RN2") (pin "8") (pinfunction "2_8") (pintype "passive"))
    )
    (net (code "123") (name "Net-(IC13-MII_MODE(RX_DV))") (class "Default")
      (node (ref "IC13") (pin "39") (pinfunction "MII_MODE(RX_DV)_39") (pintype "output"))
      (node (ref "JP13") (pin "2") (pinfunction "2_2") (pintype "passive"))
      (node (ref "RN1") (pin "6") (pinfunction "2_6") (pintype "passive"))
    )
    (net (code "124") (name "Net-(IC13-PFBIN1)") (class "Default")
      (node (ref "C60") (pin "1") (pinfunction "1_1") (pintype "passive"))
      (node (ref "C61") (pin "1") (pinfunction "1_1") (pintype "passive"))
      (node (ref "C62") (pin "+") (pinfunction "+_+") (pintype "passive"))
      (node (ref "C63") (pin "1") (pinfunction "1_1") (pintype "passive"))
      (node (ref "IC13") (pin "18") (pinfunction "PFBIN1_18") (pintype "input"))
      (node (ref "IC13") (pin "23") (pinfunction "PFBOUT_23") (pintype "output"))
      (node (ref "IC13") (pin "37") (pinfunction "PFBIN2_37") (pintype "input"))
    )
    (net (code "125") (name "Net-(IC13-PHYAD0(COL))") (class "Default")
      (node (ref "IC13") (pin "42") (pinfunction "PHYAD0(COL)_42") (pintype "output"))
      (node (ref "RN2") (pin "7") (pinfunction "2_7") (pintype "passive"))
    )
    (net (code "126") (name "Net-(IC13-PHYAD1(RXD1_0))") (class "Default")
      (node (ref "IC13") (pin "43") (pinfunction "PHYAD1(RXD1_0)_43") (pintype "output"))
      (node (ref "RN2") (pin "6") (pinfunction "2_6") (pintype "passive"))
    )
    (net (code "127") (name "Net-(IC13-PHYAD2(RXD1_1))") (class "Default")
      (node (ref "IC13") (pin "44") (pinfunction "PHYAD2(RXD1_1)_44") (pintype "output"))
      (node (ref "RN2") (pin "5") (pinfunction "2_5") (pintype "passive"))
    )
    (net (code "128") (name "Net-(IC13-PHYAD3(RXD1_2))") (class "Default")
      (node (ref "IC13") (pin "45") (pinfunction "PHYAD3(RXD1_2)_45") (pintype "output"))
      (node (ref "RN3") (pin "8") (pinfunction "2_8") (pintype "passive"))
    )
    (net (code "129") (name "Net-(IC13-PHYAD4(RXD1_3))") (class "Default")
      (node (ref "IC13") (pin "46") (pinfunction "PHYAD4(RXD1_3)_46") (pintype "output"))
      (node (ref "RN3") (pin "7") (pinfunction "2_7") (pintype "passive"))
    )
    (net (code "130") (name "Net-(IC13-PWR_DOWN{slash}INT)") (class "Default")
      (node (ref "IC13") (pin "7") (pinfunction "PWR_DOWN/INT_7") (pintype "input"))
      (node (ref "JP15") (pin "2") (pinfunction "2_2") (pintype "passive"))
    )
    (net (code "131") (name "Net-(IC13-RBIAS)") (class "Default")
      (node (ref "IC13") (pin "24") (pinfunction "RBIAS_24") (pintype "input"))
      (node (ref "R48") (pin "2") (pinfunction "2_2") (pintype "passive"))
    )
    (net (code "132") (name "Net-(IC13-RESERVED-20)") (class "Default")
      (node (ref "IC13") (pin "20") (pinfunction "RESERVED-20_20") (pintype "bidirectional"))
      (node (ref "R47") (pin "2") (pinfunction "2_2") (pintype "passive"))
    )
    (net (code "133") (name "Net-(IC13-RESERVED-21)") (class "Default")
      (node (ref "IC13") (pin "21") (pinfunction "RESERVED-21_21") (pintype "bidirectional"))
      (node (ref "R46") (pin "2") (pinfunction "2_2") (pintype "passive"))
    )
    (net (code "134") (name "Net-(IC13-RX_CLK)") (class "Default")
      (node (ref "IC13") (pin "38") (pinfunction "RX_CLK_38") (pintype "output"))
      (node (ref "RN1") (pin "7") (pinfunction "2_7") (pintype "passive"))
    )
    (net (code "135") (name "Net-(IC13-TXD_0)") (class "Default")
      (node (ref "IC13") (pin "3") (pinfunction "TXD_0_3") (pintype "input"))
      (node (ref "RN4") (pin "8") (pinfunction "2_8") (pintype "passive"))
    )
    (net (code "136") (name "Net-(IC13-TXD_1)") (class "Default")
      (node (ref "IC13") (pin "4") (pinfunction "TXD_1_4") (pintype "input"))
      (node (ref "RN4") (pin "7") (pinfunction "2_7") (pintype "passive"))
    )
    (net (code "137") (name "Net-(IC13-TXD_2)") (class "Default")
      (node (ref "IC13") (pin "5") (pinfunction "TXD_2_5") (pintype "input"))
      (node (ref "RN4") (pin "6") (pinfunction "2_6") (pintype "passive"))
    )
    (net (code "138") (name "Net-(IC13-TXD_3{slash}SNI_MODE)") (class "Default")
      (node (ref "IC13") (pin "6") (pinfunction "TXD_3/SNI_MODE_6") (pintype "input"))
      (node (ref "RN4") (pin "5") (pinfunction "2_5") (pintype "passive"))
    )
    (net (code "139") (name "Net-(IC13-TX_CLK)") (class "Default")
      (node (ref "IC13") (pin "1") (pinfunction "TX_CLK_1") (pintype "output"))
      (node (ref "RN3") (pin "6") (pinfunction "2_6") (pintype "passive"))
    )
    (net (code "140") (name "Net-(IC13-TX_EN)") (class "Default")
      (node (ref "IC13") (pin "2") (pinfunction "TX_EN_2") (pintype "input"))
      (node (ref "RN3") (pin "5") (pinfunction "2_5") (pintype "passive"))
    )
    (net (code "141") (name "Net-(IC13-X1)") (class "Default")
      (node (ref "IC13") (pin "34") (pinfunction "X1_34") (pintype "input"))
      (node (ref "RN1") (pin "8") (pinfunction "2_8") (pintype "passive"))
    )
    (net (code "142") (name "Net-(IC14-IO1)") (class "Default")
      (node (ref "IC14") (pin "1") (pinfunction "IO1_1") (pintype "bidirectional"))
      (node (ref "R3") (pin "1") (pinfunction "1_1") (pintype "passive"))
      (node (ref "X3") (pin "1") (pinfunction "1_1") (pintype "passive"))
    )
    (net (code "143") (name "Net-(IC14-IO2)") (class "Default")
      (node (ref "IC14") (pin "2") (pinfunction "IO2_2") (pintype "bidirectional"))
      (node (ref "R7") (pin "1") (pinfunction "1_1") (pintype "passive"))
      (node (ref "X3") (pin "2") (pinfunction "1_2") (pintype "passive"))
    )
    (net (code "144") (name "Net-(IC14-IO3)") (class "Default")
      (node (ref "IC1") (pin "12") (pinfunction "O_12") (pintype "output"))
      (node (ref "IC1") (pin "4") (pinfunction "O_4") (pintype "output"))
      (node (ref "IC14") (pin "4") (pinfunction "IO3_4") (pintype "bidirectional"))
      (node (ref "X3") (pin "4") (pinfunction "1_4") (pintype "passive"))
    )
    (net (code "145") (name "Net-(IC14-IO4)") (class "Default")
      (node (ref "IC1") (pin "10") (pinfunction "O_10") (pintype "output"))
      (node (ref "IC1") (pin "6") (pinfunction "O_6") (pintype "output"))
      (node (ref "IC14") (pin "5") (pinfunction "IO4_5") (pintype "bidirectional"))
      (node (ref "X3") (pin "5") (pinfunction "1_5") (pintype "passive"))
    )
    (net (code "146") (name "Net-(JP11-Pad2)") (class "Default")
      (node (ref "JP11") (pin "2") (pinfunction "2_2") (pintype "passive"))
      (node (ref "R38") (pin "2") (pinfunction "2_2") (pintype "passive"))
    )
    (net (code "147") (name "Net-(JP12-Pad1)") (class "Default")
      (node (ref "JP12") (pin "1") (pinfunction "1_1") (pintype "passive"))
      (node (ref "JP14") (pin "1") (pinfunction "1_1") (pintype "passive"))
      (node (ref "RN2") (pin "1") (pinfunction "1_1") (pintype "passive"))
    )
    (net (code "148") (name "Net-(JP12-Pad2)") (class "Default")
      (node (ref "JP12") (pin "2") (pinfunction "2_2") (pintype "passive"))
      (node (ref "R35") (pin "2") (pinfunction "2_2") (pintype "passive"))
    )
    (net (code "149") (name "Net-(JP13-Pad1)") (class "Default")
      (node (ref "JP13") (pin "1") (pinfunction "1_1") (pintype "passive"))
      (node (ref "R40") (pin "2") (pinfunction "2_2") (pintype "passive"))
    )
    (net (code "150") (name "Net-(JP15-Pad1)") (class "Default")
      (node (ref "JP15") (pin "1") (pinfunction "1_1") (pintype "passive"))
      (node (ref "R49") (pin "2") (pinfunction "2_2") (pintype "passive"))
    )
    (net (code "151") (name "Net-(LCD1-B0)") (class "Default")
      (node (ref "JP8") (pin "COM") (pinfunction "COM_COM") (pintype "passive"))
      (node (ref "LCD1") (pin "13") (pinfunction "G0_13") (pintype "input"))
      (node (ref "LCD1") (pin "14") (pinfunction "G1_14") (pintype "input"))
      (node (ref "LCD1") (pin "21") (pinfunction "B0_21") (pintype "input"))
      (node (ref "LCD1") (pin "22") (pinfunction "B1_22") (pintype "input"))
      (node (ref "LCD1") (pin "5") (pinfunction "R0_5") (pintype "input"))
      (node (ref "LCD1") (pin "6") (pinfunction "R1_6") (pintype "input"))
    )
    (net (code "152") (name "Net-(LCD1-RESET)") (class "Default")
      (node (ref "JP9") (pin "COM") (pinfunction "COM_COM") (pintype "passive"))
      (node (ref "LCD1") (pin "36") (pinfunction "RESET_36") (pintype "input"))
    )
    (net (code "153") (name "Net-(Q1-PadB)") (class "Default")
      (node (ref "Q1") (pin "B") (pinfunction "B_B") (pintype "passive"))
      (node (ref "R28") (pin "2") (pinfunction "2_2") (pintype "passive"))
    )
    (net (code "154") (name "Net-(Q1-PadC)") (class "Default")
      (node (ref "Q1") (pin "C") (pinfunction "C_C") (pintype "passive"))
      (node (ref "R25") (pin "1") (pinfunction "1_1") (pintype "passive"))
    )
    (net (code "155") (name "Net-(Q2-D)") (class "Default")
      (node (ref "Q2") (pin "3") (pinfunction "D_3") (pintype "passive"))
      (node (ref "SP1") (pin "-B") (pinfunction "-_-B") (pintype "passive"))
      (node (ref "SP1") (pin "-B.1") (pinfunction "-_-B.1") (pintype "passive"))
    )
    (net (code "156") (name "Net-(R1-Pad2)") (class "Default")
      (node (ref "R1") (pin "2") (pinfunction "2_2") (pintype "passive"))
      (node (ref "R2") (pin "2") (pinfunction "2_2") (pintype "passive"))
      (node (ref "SW2") (pin "A") (pinfunction "A_A") (pintype "passive"))
    )
    (net (code "157") (name "Net-(R3-Pad2)") (class "Default")
      (node (ref "R3") (pin "2") (pinfunction "2_2") (pintype "passive"))
      (node (ref "R4") (pin "1") (pinfunction "1_1") (pintype "passive"))
    )
    (net (code "158") (name "Net-(R7-Pad2)") (class "Default")
      (node (ref "R7") (pin "2") (pinfunction "2_2") (pintype "passive"))
      (node (ref "R8") (pin "1") (pinfunction "1_1") (pintype "passive"))
    )
    (net (code "159") (name "Net-(R10-Pad2)") (class "Default")
      (node (ref "R10") (pin "2") (pinfunction "2_2") (pintype "passive"))
      (node (ref "R6") (pin "2") (pinfunction "2_2") (pintype "passive"))
      (node (ref "SW2") (pin "B") (pinfunction "B_B") (pintype "passive"))
    )
    (net (code "160") (name "Net-(R25-Pad2)") (class "Default")
      (node (ref "R25") (pin "2") (pinfunction "2_2") (pintype "passive"))
      (node (ref "VBUS") (pin "C") (pinfunction "C_C") (pintype "passive"))
    )
    (net (code "161") (name "Net-(R39-Pad2)") (class "Default")
      (node (ref "R39") (pin "2") (pinfunction "2_2") (pintype "passive"))
      (node (ref "SPEED") (pin "A") (pinfunction "A_A") (pintype "passive"))
    )
    (net (code "162") (name "Net-(X2E-1)") (class "Default")
      (node (ref "SCL") (pin "2") (pinfunction "2_2") (pintype "passive"))
      (node (ref "X2") (pin "13") (pinfunction "1_13") (pintype "passive"))
    )
    (net (code "163") (name "Net-(X2F-1)") (class "Default")
      (node (ref "SDA") (pin "1") (pinfunction "1_1") (pintype "passive"))
      (node (ref "X2") (pin "14") (pinfunction "1_14") (pintype "passive"))
    )
    (net (code "164") (name "Net-(X4A-S)") (class "Default")
      (node (ref "JP7") (pin "2") (pinfunction "2_2") (pintype "passive"))
      (node (ref "R18") (pin "2") (pinfunction "2_2") (pintype "passive"))
      (node (ref "X4") (pin "1") (pinfunction "S_1") (pintype "passive"))
    )
    (net (code "165") (name "Net-(X5-GREEN-C)") (class "Default")
      (node (ref "R45") (pin "1") (pinfunction "1_1") (pintype "passive"))
      (node (ref "X5") (pin "10") (pinfunction "GREEN-C_10") (pintype "passive"))
    )
    (net (code "166") (name "Net-(X5-YELLOW-C)") (class "Default")
      (node (ref "R44") (pin "1") (pinfunction "1_1") (pintype "passive"))
      (node (ref "X5") (pin "11") (pinfunction "YELLOW-C_11") (pintype "passive"))
    )
    (net (code "167") (name "OE_SYNC") (class "Default")
      (node (ref "IC2") (pin "94") (pinfunction "PD13_94") (pintype "bidirectional"))
      (node (ref "X1") (pin "10") (pinfunction "1_10") (pintype "passive"))
    )
    (net (code "168") (name "PE") (class "Default")
      (node (ref "C1") (pin "1") (pinfunction "1_1") (pintype "passive"))
      (node (ref "C49") (pin "1") (pinfunction "1_1") (pintype "passive"))
      (node (ref "J2") (pin "SH1") (pinfunction "SH1_SH1") (pintype "bidirectional"))
      (node (ref "J2") (pin "SH1.1") (pinfunction "SH1_SH1.1") (pintype "bidirectional"))
      (node (ref "J2") (pin "SH2") (pinfunction "SH2_SH2") (pintype "bidirectional"))
      (node (ref "J2") (pin "SH2.2") (pinfunction "SH2_SH2.2") (pintype "bidirectional"))
      (node (ref "JP1") (pin "2") (pinfunction "2_2") (pintype "passive"))
      (node (ref "X2") (pin "1") (pinfunction "1_1") (pintype "passive"))
      (node (ref "X5") (pin "SH") (pinfunction "SH_SH") (pintype "passive"))
      (node (ref "X5") (pin "SH2") (pinfunction "SH_SH2") (pintype "passive"))
    )
    (net (code "169") (name "PWR_DIRECT") (class "Default")
      (node (ref "IC2") (pin "110") (pinfunction "PG2_110") (pintype "bidirectional"))
      (node (ref "X2") (pin "12") (pinfunction "1_12") (pintype "passive"))
    )
    (net (code "170") (name "PWR_SSTART") (class "Default")
      (node (ref "IC2") (pin "111") (pinfunction "PG3_111") (pintype "bidirectional"))
      (node (ref "X2") (pin "11") (pinfunction "1_11") (pintype "passive"))
    )
    (net (code "171") (name "RCC_OSC32_IN") (class "Default")
      (node (ref "C8") (pin "1") (pinfunction "1_1") (pintype "passive"))
      (node (ref "IC2") (pin "9") (pinfunction "PC14_9") (pintype "bidirectional"))
      (node (ref "Y2") (pin "1") (pinfunction "1_1") (pintype "passive"))
    )
    (net (code "172") (name "RCC_OSC32_OUT") (class "Default")
      (node (ref "C10") (pin "1") (pinfunction "1_1") (pintype "passive"))
      (node (ref "IC2") (pin "10") (pinfunction "PC15_10") (pintype "bidirectional"))
      (node (ref "Y2") (pin "4") (pinfunction "2_4") (pintype "passive"))
    )
    (net (code "173") (name "RCC_OSC_IN") (class "Default")
      (node (ref "C7") (pin "2") (pinfunction "2_2") (pintype "passive"))
      (node (ref "IC2") (pin "29") (pinfunction "PH0_29") (pintype "bidirectional"))
      (node (ref "Y1") (pin "2") (pinfunction "2_2") (pintype "passive"))
    )
    (net (code "174") (name "RCC_OSC_OUT") (class "Default")
      (node (ref "C9") (pin "2") (pinfunction "2_2") (pintype "passive"))
      (node (ref "IC2") (pin "30") (pinfunction "PH1_30") (pintype "bidirectional"))
      (node (ref "Y1") (pin "1") (pinfunction "1_1") (pintype "passive"))
    )
    (net (code "175") (name "SDMMC1_CK") (class "Default")
      (node (ref "IC2") (pin "141") (pinfunction "PC12_141") (pintype "bidirectional"))
      (node (ref "J1") (pin "5") (pinfunction "CLK_5") (pintype "passive"))
    )
    (net (code "176") (name "SDMMC1_CMD") (class "Default")
      (node (ref "IC2") (pin "144") (pinfunction "PD2_144") (pintype "bidirectional"))
      (node (ref "J1") (pin "3") (pinfunction "CMD_3") (pintype "passive"))
      (node (ref "R22") (pin "2") (pinfunction "2_2") (pintype "passive"))
    )
    (net (code "177") (name "SDMMC1_D0") (class "Default")
      (node (ref "IC2") (pin "121") (pinfunction "PC8_121") (pintype "bidirectional"))
      (node (ref "J1") (pin "7") (pinfunction "DAT0_7") (pintype "passive"))
      (node (ref "R21") (pin "2") (pinfunction "2_2") (pintype "passive"))
    )
    (net (code "178") (name "SD_DETECT") (class "Default")
      (node (ref "IC2") (pin "140") (pinfunction "PC11_140") (pintype "bidirectional"))
      (node (ref "J1") (pin "SW1") (pinfunction "SW1_SW1") (pintype "passive"))
    )
    (net (code "179") (name "SPI2_CLK") (class "Default")
      (node (ref "IC2") (pin "133") (pinfunction "PI1_133") (pintype "bidirectional"))
      (node (ref "X1") (pin "32") (pinfunction "1_32") (pintype "passive"))
    )
    (net (code "180") (name "SPI2_CSA") (class "Default")
      (node (ref "IC2") (pin "93") (pinfunction "PD12_93") (pintype "bidirectional"))
      (node (ref "X1") (pin "28") (pinfunction "1_28") (pintype "passive"))
    )
    (net (code "181") (name "SPI2_CSB") (class "Default")
      (node (ref "IC2") (pin "92") (pinfunction "PD11_92") (pintype "bidirectional"))
      (node (ref "X1") (pin "27") (pinfunction "1_27") (pintype "passive"))
    )
    (net (code "182") (name "SPI2_IRQ") (class "Default")
      (node (ref "IC2") (pin "123") (pinfunction "PA8_123") (pintype "bidirectional"))
      (node (ref "X1") (pin "25") (pinfunction "1_25") (pintype "passive"))
    )
    (net (code "183") (name "SPI2_MISO") (class "Default")
      (node (ref "IC2") (pin "87") (pinfunction "PB14_87") (pintype "bidirectional"))
      (node (ref "X1") (pin "31") (pinfunction "1_31") (pintype "passive"))
    )
    (net (code "184") (name "SPI2_MOSI") (class "Default")
      (node (ref "IC2") (pin "134") (pinfunction "PI3_134") (pintype "bidirectional"))
      (node (ref "X1") (pin "33") (pinfunction "1_33") (pintype "passive"))
    )
    (net (code "185") (name "SPI4_CLK") (class "Default")
      (node (ref "IC2") (pin "1") (pinfunction "PE2_1") (pintype "bidirectional"))
      (node (ref "X1") (pin "23") (pinfunction "1_23") (pintype "passive"))
    )
    (net (code "186") (name "SPI4_CSA") (class "Default")
      (node (ref "IC2") (pin "2") (pinfunction "PE3_2") (pintype "bidirectional"))
      (node (ref "X1") (pin "22") (pinfunction "1_22") (pintype "passive"))
    )
    (net (code "187") (name "SPI4_CSB") (class "Default")
      (node (ref "IC2") (pin "3") (pinfunction "PE4_3") (pintype "bidirectional"))
      (node (ref "X1") (pin "21") (pinfunction "1_21") (pintype "passive"))
    )
    (net (code "188") (name "SPI4_IRQ") (class "Default")
      (node (ref "IC2") (pin "168") (pinfunction "PB9_168") (pintype "bidirectional"))
      (node (ref "X1") (pin "19") (pinfunction "1_19") (pintype "passive"))
    )
    (net (code "189") (name "SPI4_MISO") (class "Default")
      (node (ref "IC2") (pin "4") (pinfunction "PE5_4") (pintype "bidirectional"))
      (node (ref "X1") (pin "24") (pinfunction "1_24") (pintype "passive"))
    )
    (net (code "190") (name "SPI4_MOSI") (class "Default")
      (node (ref "IC2") (pin "5") (pinfunction "PE6_5") (pintype "bidirectional"))
      (node (ref "X1") (pin "26") (pinfunction "1_26") (pintype "passive"))
    )
    (net (code "191") (name "SPI5_CLK") (class "Default")
      (node (ref "IC2") (pin "25") (pinfunction "PF7_25") (pintype "bidirectional"))
      (node (ref "X1") (pin "17") (pinfunction "1_17") (pintype "passive"))
    )
    (net (code "192") (name "SPI5_CSA") (class "Default")
      (node (ref "IC2") (pin "157") (pinfunction "PG14_157") (pintype "bidirectional"))
      (node (ref "X1") (pin "11") (pinfunction "1_11") (pintype "passive"))
    )
    (net (code "193") (name "SPI5_CSB") (class "Default")
      (node (ref "IC2") (pin "156") (pinfunction "PG13_156") (pintype "bidirectional"))
      (node (ref "X1") (pin "13") (pinfunction "1_13") (pintype "passive"))
    )
    (net (code "194") (name "SPI5_IRQ") (class "Default")
      (node (ref "IC2") (pin "138") (pinfunction "PA15_138") (pintype "bidirectional"))
      (node (ref "X1") (pin "9") (pinfunction "1_9") (pintype "passive"))
    )
    (net (code "195") (name "SPI5_MISO") (class "Default")
      (node (ref "IC2") (pin "26") (pinfunction "PF8_26") (pintype "bidirectional"))
      (node (ref "X1") (pin "18") (pinfunction "1_18") (pintype "passive"))
    )
    (net (code "196") (name "SPI5_MOSI") (class "Default")
      (node (ref "IC2") (pin "27") (pinfunction "PF9_27") (pintype "bidirectional"))
      (node (ref "X1") (pin "20") (pinfunction "1_20") (pintype "passive"))
    )
    (net (code "197") (name "SYS_JTCK-SWCLK") (class "Default")
      (node (ref "IC2") (pin "137") (pinfunction "PA14_137") (pintype "bidirectional"))
      (node (ref "R20") (pin "1") (pinfunction "1_1") (pintype "passive"))
    )
    (net (code "198") (name "SYS_JTDO-SWO") (class "Default")
      (node (ref "IC2") (pin "161") (pinfunction "PB3_161") (pintype "bidirectional"))
      (node (ref "IC4") (pin "5") (pinfunction "IO4_5") (pintype "bidirectional"))
      (node (ref "X4") (pin "6") (pinfunction "S_6") (pintype "passive"))
    )
    (net (code "199") (name "SYS_JTMS-SWDIO") (class "Default")
      (node (ref "IC2") (pin "128") (pinfunction "PA13_128") (pintype "bidirectional"))
      (node (ref "R19") (pin "1") (pinfunction "1_1") (pintype "passive"))
    )
    (net (code "200") (name "TCK") (class "Default")
      (node (ref "IC4") (pin "1") (pinfunction "IO1_1") (pintype "bidirectional"))
      (node (ref "R20") (pin "2") (pinfunction "2_2") (pintype "passive"))
      (node (ref "X4") (pin "2") (pinfunction "S_2") (pintype "passive"))
    )
    (net (code "201") (name "TFT_BRIGHTNESS") (class "Default")
      (node (ref "IC2") (pin "88") (pinfunction "PB15_88") (pintype "bidirectional"))
      (node (ref "IC8") (pin "4") (pinfunction "CTRL_4") (pintype "input"))
    )
    (net (code "202") (name "TMS") (class "Default")
      (node (ref "IC4") (pin "2") (pinfunction "IO2_2") (pintype "bidirectional"))
      (node (ref "R19") (pin "2") (pinfunction "2_2") (pintype "passive"))
      (node (ref "X4") (pin "4") (pinfunction "S_4") (pintype "passive"))
    )
    (net (code "203") (name "UART_RX{slash}DIN1") (class "Default")
      (node (ref "IC2") (pin "24") (pinfunction "PF6_24") (pintype "bidirectional"))
      (node (ref "R5") (pin "2") (pinfunction "2_2") (pintype "passive"))
      (node (ref "X1") (pin "3") (pinfunction "1_3") (pintype "passive"))
    )
    (net (code "204") (name "UART_TX{slash}DOUT1") (class "Default")
      (node (ref "IC1") (pin "11") (pinfunction "I_11") (pintype "input"))
      (node (ref "IC1") (pin "5") (pinfunction "I_5") (pintype "input"))
      (node (ref "IC2") (pin "162") (pinfunction "PB4_162") (pintype "bidirectional"))
      (node (ref "X1") (pin "4") (pinfunction "1_4") (pintype "passive"))
    )
    (net (code "205") (name "USB_D_N") (class "Default")
      (node (ref "IC9") (pin "1") (pinfunction "IO1_1") (pintype "bidirectional"))
      (node (ref "J2") (pin "2") (pinfunction "D-_2") (pintype "passive"))
      (node (ref "R29") (pin "1") (pinfunction "1_1") (pintype "passive"))
    )
    (net (code "206") (name "USB_D_P") (class "Default")
      (node (ref "IC9") (pin "2") (pinfunction "IO2_2") (pintype "bidirectional"))
      (node (ref "J2") (pin "3") (pinfunction "D+_3") (pintype "passive"))
      (node (ref "R30") (pin "1") (pinfunction "1_1") (pintype "passive"))
    )
    (net (code "207") (name "USB_OTG_FS_D_N") (class "Default")
      (node (ref "IC2") (pin "126") (pinfunction "PA11_126") (pintype "bidirectional"))
      (node (ref "R29") (pin "2") (pinfunction "2_2") (pintype "passive"))
    )
    (net (code "208") (name "USB_OTG_FS_D_P") (class "Default")
      (node (ref "IC2") (pin "127") (pinfunction "PA12_127") (pintype "bidirectional"))
      (node (ref "R30") (pin "2") (pinfunction "2_2") (pintype "passive"))
    )
    (net (code "209") (name "USB_OTG_FS_ID") (class "Default")
      (node (ref "IC2") (pin "125") (pinfunction "PA10_125") (pintype "bidirectional"))
      (node (ref "IC9") (pin "4") (pinfunction "IO3_4") (pintype "bidirectional"))
      (node (ref "J2") (pin "4") (pinfunction "ID_4") (pintype "passive"))
    )
    (net (code "210") (name "USB_OTG_FS_PSO") (class "Default")
      (node (ref "IC2") (pin "147") (pinfunction "PD5_147") (pintype "bidirectional"))
      (node (ref "IC7") (pin "4") (pinfunction "EN_4") (pintype "input"))
    )
    (net (code "211") (name "USB_OTG_FS_VBUS") (class "Default")
      (node (ref "C47") (pin "+") (pinfunction "+_+") (pintype "passive"))
      (node (ref "C50") (pin "2") (pinfunction "2_2") (pintype "passive"))
      (node (ref "IC2") (pin "124") (pinfunction "PA9_124") (pintype "bidirectional"))
      (node (ref "IC7") (pin "1") (pinfunction "OUT_1") (pintype "output"))
      (node (ref "IC9") (pin "6") (pinfunction "VCC_6") (pintype "passive"))
      (node (ref "J2") (pin "1") (pinfunction "VCC_1") (pintype "passive"))
      (node (ref "R28") (pin "1") (pinfunction "1_1") (pintype "passive"))
    )
    (net (code "212") (name "USER_SW") (class "Default")
      (node (ref "C3") (pin "2") (pinfunction "2_2") (pintype "passive"))
      (node (ref "IC2") (pin "152") (pinfunction "PG9_152") (pintype "bidirectional"))
      (node (ref "SW1") (pin "1") (pinfunction "1_1") (pintype "passive"))
    )
    (net (code "213") (name "VBAT") (class "Default")
      (node (ref "IC2") (pin "6") (pinfunction "VBAT_6") (pintype "power_in"))
      (node (ref "JP6") (pin "COM") (pinfunction "COM_COM") (pintype "passive"))
    )
    (net (code "214") (name "VCAP1") (class "Default")
      (node (ref "C35") (pin "1") (pinfunction "1_1") (pintype "passive"))
      (node (ref "IC2") (pin "81") (pinfunction "VCAP_1_81") (pintype "power_in"))
    )
    (net (code "215") (name "VCAP2") (class "Default")
      (node (ref "C34") (pin "1") (pinfunction "1_1") (pintype "passive"))
      (node (ref "IC2") (pin "129") (pinfunction "VCAP_2_129") (pintype "power_in"))
    )
    (net (code "216") (name "VDD") (class "Default")
      (node (ref "C14") (pin "1") (pinfunction "1_1") (pintype "passive"))
      (node (ref "C15") (pin "1") (pinfunction "1_1") (pintype "passive"))
      (node (ref "C16") (pin "1") (pinfunction "1_1") (pintype "passive"))
      (node (ref "C17") (pin "1") (pinfunction "1_1") (pintype "passive"))
      (node (ref "C18") (pin "1") (pinfunction "1_1") (pintype "passive"))
      (node (ref "C19") (pin "1") (pinfunction "1_1") (pintype "passive"))
      (node (ref "C20") (pin "+") (pinfunction "+_+") (pintype "passive"))
      (node (ref "C21") (pin "1") (pinfunction "1_1") (pintype "passive"))
      (node (ref "C22") (pin "1") (pinfunction "1_1") (pintype "passive"))
      (node (ref "C23") (pin "1") (pinfunction "1_1") (pintype "passive"))
      (node (ref "C24") (pin "1") (pinfunction "1_1") (pintype "passive"))
      (node (ref "C25") (pin "1") (pinfunction "1_1") (pintype "passive"))
      (node (ref "C26") (pin "1") (pinfunction "1_1") (pintype "passive"))
      (node (ref "C27") (pin "1") (pinfunction "1_1") (pintype "passive"))
      (node (ref "C28") (pin "1") (pinfunction "1_1") (pintype "passive"))
      (node (ref "C29") (pin "1") (pinfunction "1_1") (pintype "passive"))
      (node (ref "C30") (pin "1") (pinfunction "1_1") (pintype "passive"))
      (node (ref "C31") (pin "1") (pinfunction "1_1") (pintype "passive"))
      (node (ref "FB1") (pin "P$1") (pinfunction "1_P$1") (pintype "passive"))
      (node (ref "IC2") (pin "118") (pinfunction "VDDUSB_118") (pintype "power_in"))
      (node (ref "IC2") (pin "131") (pinfunction "VDD_10_131") (pintype "power_in"))
      (node (ref "IC2") (pin "136") (pinfunction "VDD_11_136") (pintype "power_in"))
      (node (ref "IC2") (pin "149") (pinfunction "VDDSDMMC_149") (pintype "power_in"))
      (node (ref "IC2") (pin "15") (pinfunction "VDD_2_15") (pintype "power_in"))
      (node (ref "IC2") (pin "159") (pinfunction "VDD_12_159") (pintype "power_in"))
      (node (ref "IC2") (pin "171") (pinfunction "PDR_ON_171") (pintype "passive"))
      (node (ref "IC2") (pin "172") (pinfunction "VDD_172") (pintype "power_in"))
      (node (ref "IC2") (pin "23") (pinfunction "VDD_3_23") (pintype "power_in"))
      (node (ref "IC2") (pin "36") (pinfunction "VDD_4_36") (pintype "power_in"))
      (node (ref "IC2") (pin "49") (pinfunction "VDD_5_49") (pintype "power_in"))
      (node (ref "IC2") (pin "62") (pinfunction "VDD_6_62") (pintype "power_in"))
      (node (ref "IC2") (pin "72") (pinfunction "VDD_7_72") (pintype "power_in"))
      (node (ref "IC2") (pin "82") (pinfunction "VDD_8_82") (pintype "power_in"))
      (node (ref "IC2") (pin "96") (pinfunction "VDD_9_96") (pintype "power_in"))
      (node (ref "IC2") (pin "99") (pinfunction "VDDDSI_99") (pintype "power_in"))
      (node (ref "JP4") (pin "1") (pinfunction "1_1") (pintype "passive"))
      (node (ref "JP6") (pin "NO") (pinfunction "NO_NO") (pintype "passive"))
      (node (ref "R11") (pin "1") (pinfunction "1_1") (pintype "passive"))
    )
    (net (code "217") (name "VDDA") (class "Default")
      (node (ref "C32") (pin "1") (pinfunction "1_1") (pintype "passive"))
      (node (ref "C33") (pin "1") (pinfunction "1_1") (pintype "passive"))
      (node (ref "FB1") (pin "P$2") (pinfunction "2_P$2") (pintype "passive"))
      (node (ref "IC2") (pin "39") (pinfunction "VDDA_39") (pintype "power_in"))
      (node (ref "R17") (pin "2") (pinfunction "2_2") (pintype "passive"))
    )
    (net (code "218") (name "VLED+") (class "Default")
      (node (ref "C46") (pin "1") (pinfunction "1_1") (pintype "passive"))
      (node (ref "D2") (pin "C") (pinfunction "C_C") (pintype "passive"))
      (node (ref "LCD1") (pin "2") (pinfunction "VLED+_2") (pintype "power_in"))
      (node (ref "ZD1") (pin "C") (pinfunction "C_C") (pintype "passive"))
    )
    (net (code "219") (name "VLED-") (class "Default")
      (node (ref "IC8") (pin "3") (pinfunction "FB_3") (pintype "input"))
      (node (ref "LCD1") (pin "1") (pinfunction "VLED-_1") (pintype "power_in"))
      (node (ref "R26") (pin "1") (pinfunction "1_1") (pintype "passive"))
      (node (ref "ZD1") (pin "A") (pinfunction "A_A") (pintype "passive"))
    )
    (net (code "220") (name "VREF+") (class "Default")
      (node (ref "IC2") (pin "38") (pinfunction "VREF+_38") (pintype "power_in"))
      (node (ref "R17") (pin "1") (pinfunction "1_1") (pintype "passive"))
    )
    (net (code "221") (name "XL") (class "Default")
      (node (ref "IC10") (pin "4") (pinfunction "IO3_4") (pintype "bidirectional"))
      (node (ref "IC11") (pin "4") (pinfunction "X-_4") (pintype "input"))
      (node (ref "LCD1") (pin "39") (pinfunction "XL_39") (pintype "passive"))
    )
    (net (code "222") (name "XR") (class "Default")
      (node (ref "IC10") (pin "1") (pinfunction "IO1_1") (pintype "bidirectional"))
      (node (ref "IC11") (pin "2") (pinfunction "X+_2") (pintype "input"))
      (node (ref "LCD1") (pin "37") (pinfunction "XR_37") (pintype "passive"))
    )
    (net (code "223") (name "YD") (class "Default")
      (node (ref "IC10") (pin "2") (pinfunction "IO2_2") (pintype "bidirectional"))
      (node (ref "IC11") (pin "5") (pinfunction "Y-_5") (pintype "input"))
      (node (ref "LCD1") (pin "38") (pinfunction "YD_38") (pintype "passive"))
    )
    (net (code "224") (name "YU") (class "Default")
      (node (ref "IC10") (pin "5") (pinfunction "IO4_5") (pintype "bidirectional"))
      (node (ref "IC11") (pin "3") (pinfunction "Y+_3") (pintype "input"))
      (node (ref "LCD1") (pin "40") (pinfunction "YU_40") (pintype "passive"))
    )
    (net (code "225") (name "unconnected-(IC2C-DSI_CKN-Pad105)") (class "Default")
      (node (ref "IC2") (pin "105") (pinfunction "DSI_CKN_105") (pintype "bidirectional"))
    )
    (net (code "226") (name "unconnected-(IC2C-DSI_CKP-Pad104)") (class "Default")
      (node (ref "IC2") (pin "104") (pinfunction "DSI_CKP_104") (pintype "bidirectional"))
    )
    (net (code "227") (name "unconnected-(IC2C-DSI_D0N-Pad102)") (class "Default")
      (node (ref "IC2") (pin "102") (pinfunction "DSI_D0N_102") (pintype "bidirectional"))
    )
    (net (code "228") (name "unconnected-(IC2C-DSI_D0P-Pad101)") (class "Default")
      (node (ref "IC2") (pin "101") (pinfunction "DSI_D0P_101") (pintype "bidirectional"))
    )
    (net (code "229") (name "unconnected-(IC2C-DSI_D1N-Pad108)") (class "Default")
      (node (ref "IC2") (pin "108") (pinfunction "DSI_D1N_108") (pintype "bidirectional"))
    )
    (net (code "230") (name "unconnected-(IC2C-DSI_D1P-Pad107)") (class "Default")
      (node (ref "IC2") (pin "107") (pinfunction "DSI_D1P_107") (pintype "bidirectional"))
    )
    (net (code "231") (name "unconnected-(IC2C-PI8-Pad7)") (class "Default")
      (node (ref "IC2") (pin "7") (pinfunction "PI8_7") (pintype "bidirectional"))
    )
    (net (code "232") (name "unconnected-(IC5-A12{slash}NC-36-Pad36)") (class "Default")
      (node (ref "IC5") (pin "36") (pinfunction "A12/NC-36_36") (pintype "passive"))
    )
    (net (code "233") (name "unconnected-(IC5-NC-40-Pad40)") (class "Default")
      (node (ref "IC5") (pin "40") (pinfunction "NC-40_40") (pintype "no_connect"))
    )
    (net (code "234") (name "unconnected-(IC9-IO4-Pad5)") (class "Default")
      (node (ref "IC9") (pin "5") (pinfunction "IO4_5") (pintype "bidirectional"))
    )
    (net (code "235") (name "unconnected-(IC11-AUX-Pad16)") (class "Default")
      (node (ref "IC11") (pin "16") (pinfunction "AUX_16") (pintype "input"))
    )
    (net (code "236") (name "unconnected-(IC13-CLK_OUT-Pad25)") (class "Default")
      (node (ref "IC13") (pin "25") (pinfunction "CLK_OUT_25") (pintype "output"))
    )
    (net (code "237") (name "unconnected-(IC13-TCK-Pad8)") (class "Default")
      (node (ref "IC13") (pin "8") (pinfunction "TCK_8") (pintype "input"))
    )
    (net (code "238") (name "unconnected-(IC13-TDI-Pad12)") (class "Default")
      (node (ref "IC13") (pin "12") (pinfunction "TDI_12") (pintype "input"))
    )
    (net (code "239") (name "unconnected-(IC13-TDO-Pad9)") (class "Default")
      (node (ref "IC13") (pin "9") (pinfunction "TDO_9") (pintype "output"))
    )
    (net (code "240") (name "unconnected-(IC13-TMS-Pad10)") (class "Default")
      (node (ref "IC13") (pin "10") (pinfunction "TMS_10") (pintype "input"))
    )
    (net (code "241") (name "unconnected-(IC13-X2-Pad33)") (class "Default")
      (node (ref "IC13") (pin "33") (pinfunction "X2_33") (pintype "output"))
    )
    (net (code "242") (name "unconnected-(IC13-~{TRST}-Pad11)") (class "Default")
      (node (ref "IC13") (pin "11") (pinfunction "~{TRST}_11") (pintype "input"))
    )
    (net (code "243") (name "unconnected-(J1-CD{slash}DAT3-Pad2)") (class "Default")
      (node (ref "J1") (pin "2") (pinfunction "CD/DAT3_2") (pintype "passive"))
    )
    (net (code "244") (name "unconnected-(J1-DAT1-Pad8)") (class "Default")
      (node (ref "J1") (pin "8") (pinfunction "DAT1_8") (pintype "passive"))
    )
    (net (code "245") (name "unconnected-(J1-DAT2-Pad1)") (class "Default")
      (node (ref "J1") (pin "1") (pinfunction "DAT2_1") (pintype "passive"))
    )
    (net (code "246") (name "unconnected-(LCD1-NC1-Pad35)") (class "Default")
      (node (ref "LCD1") (pin "35") (pinfunction "NC1_35") (pintype "no_connect"))
    )
    (net (code "247") (name "~{FAULT}") (class "Default")
      (node (ref "IC2") (pin "58") (pinfunction "PB2_58") (pintype "bidirectional"))
      (node (ref "R14") (pin "2") (pinfunction "2_2") (pintype "passive"))
      (node (ref "X1") (pin "8") (pinfunction "1_8") (pintype "passive"))
      (node (ref "X2") (pin "15") (pinfunction "1_15") (pintype "passive"))
    )
    (net (code "248") (name "~{RESET}") (class "Default")
      (node (ref "IC13") (pin "29") (pinfunction "RESET_N_29") (pintype "input"))
      (node (ref "IC2") (pin "31") (pinfunction "NRST_31") (pintype "bidirectional"))
      (node (ref "IC4") (pin "4") (pinfunction "IO3_4") (pintype "bidirectional"))
      (node (ref "JP9") (pin "NO") (pinfunction "NO_NO") (pintype "passive"))
      (node (ref "R11") (pin "2") (pinfunction "2_2") (pintype "passive"))
      (node (ref "X1") (pin "6") (pinfunction "1_6") (pintype "passive"))
      (node (ref "X4") (pin "5") (pinfunction "S_5") (pintype "passive"))
    )
    (net (code "249") (name "~{USB_OTG_FS_OC}") (class "Default")
      (node (ref "IC2") (pin "146") (pinfunction "PD4_146") (pintype "bidirectional"))
      (node (ref "IC7") (pin "3") (pinfunction "~{OC}_3") (pintype "passive"))
      (node (ref "R27") (pin "1") (pinfunction "1_1") (pintype "passive"))
    )
  )
)
